# router.net
KiCad netlist of a schematic drawn in EAGLE
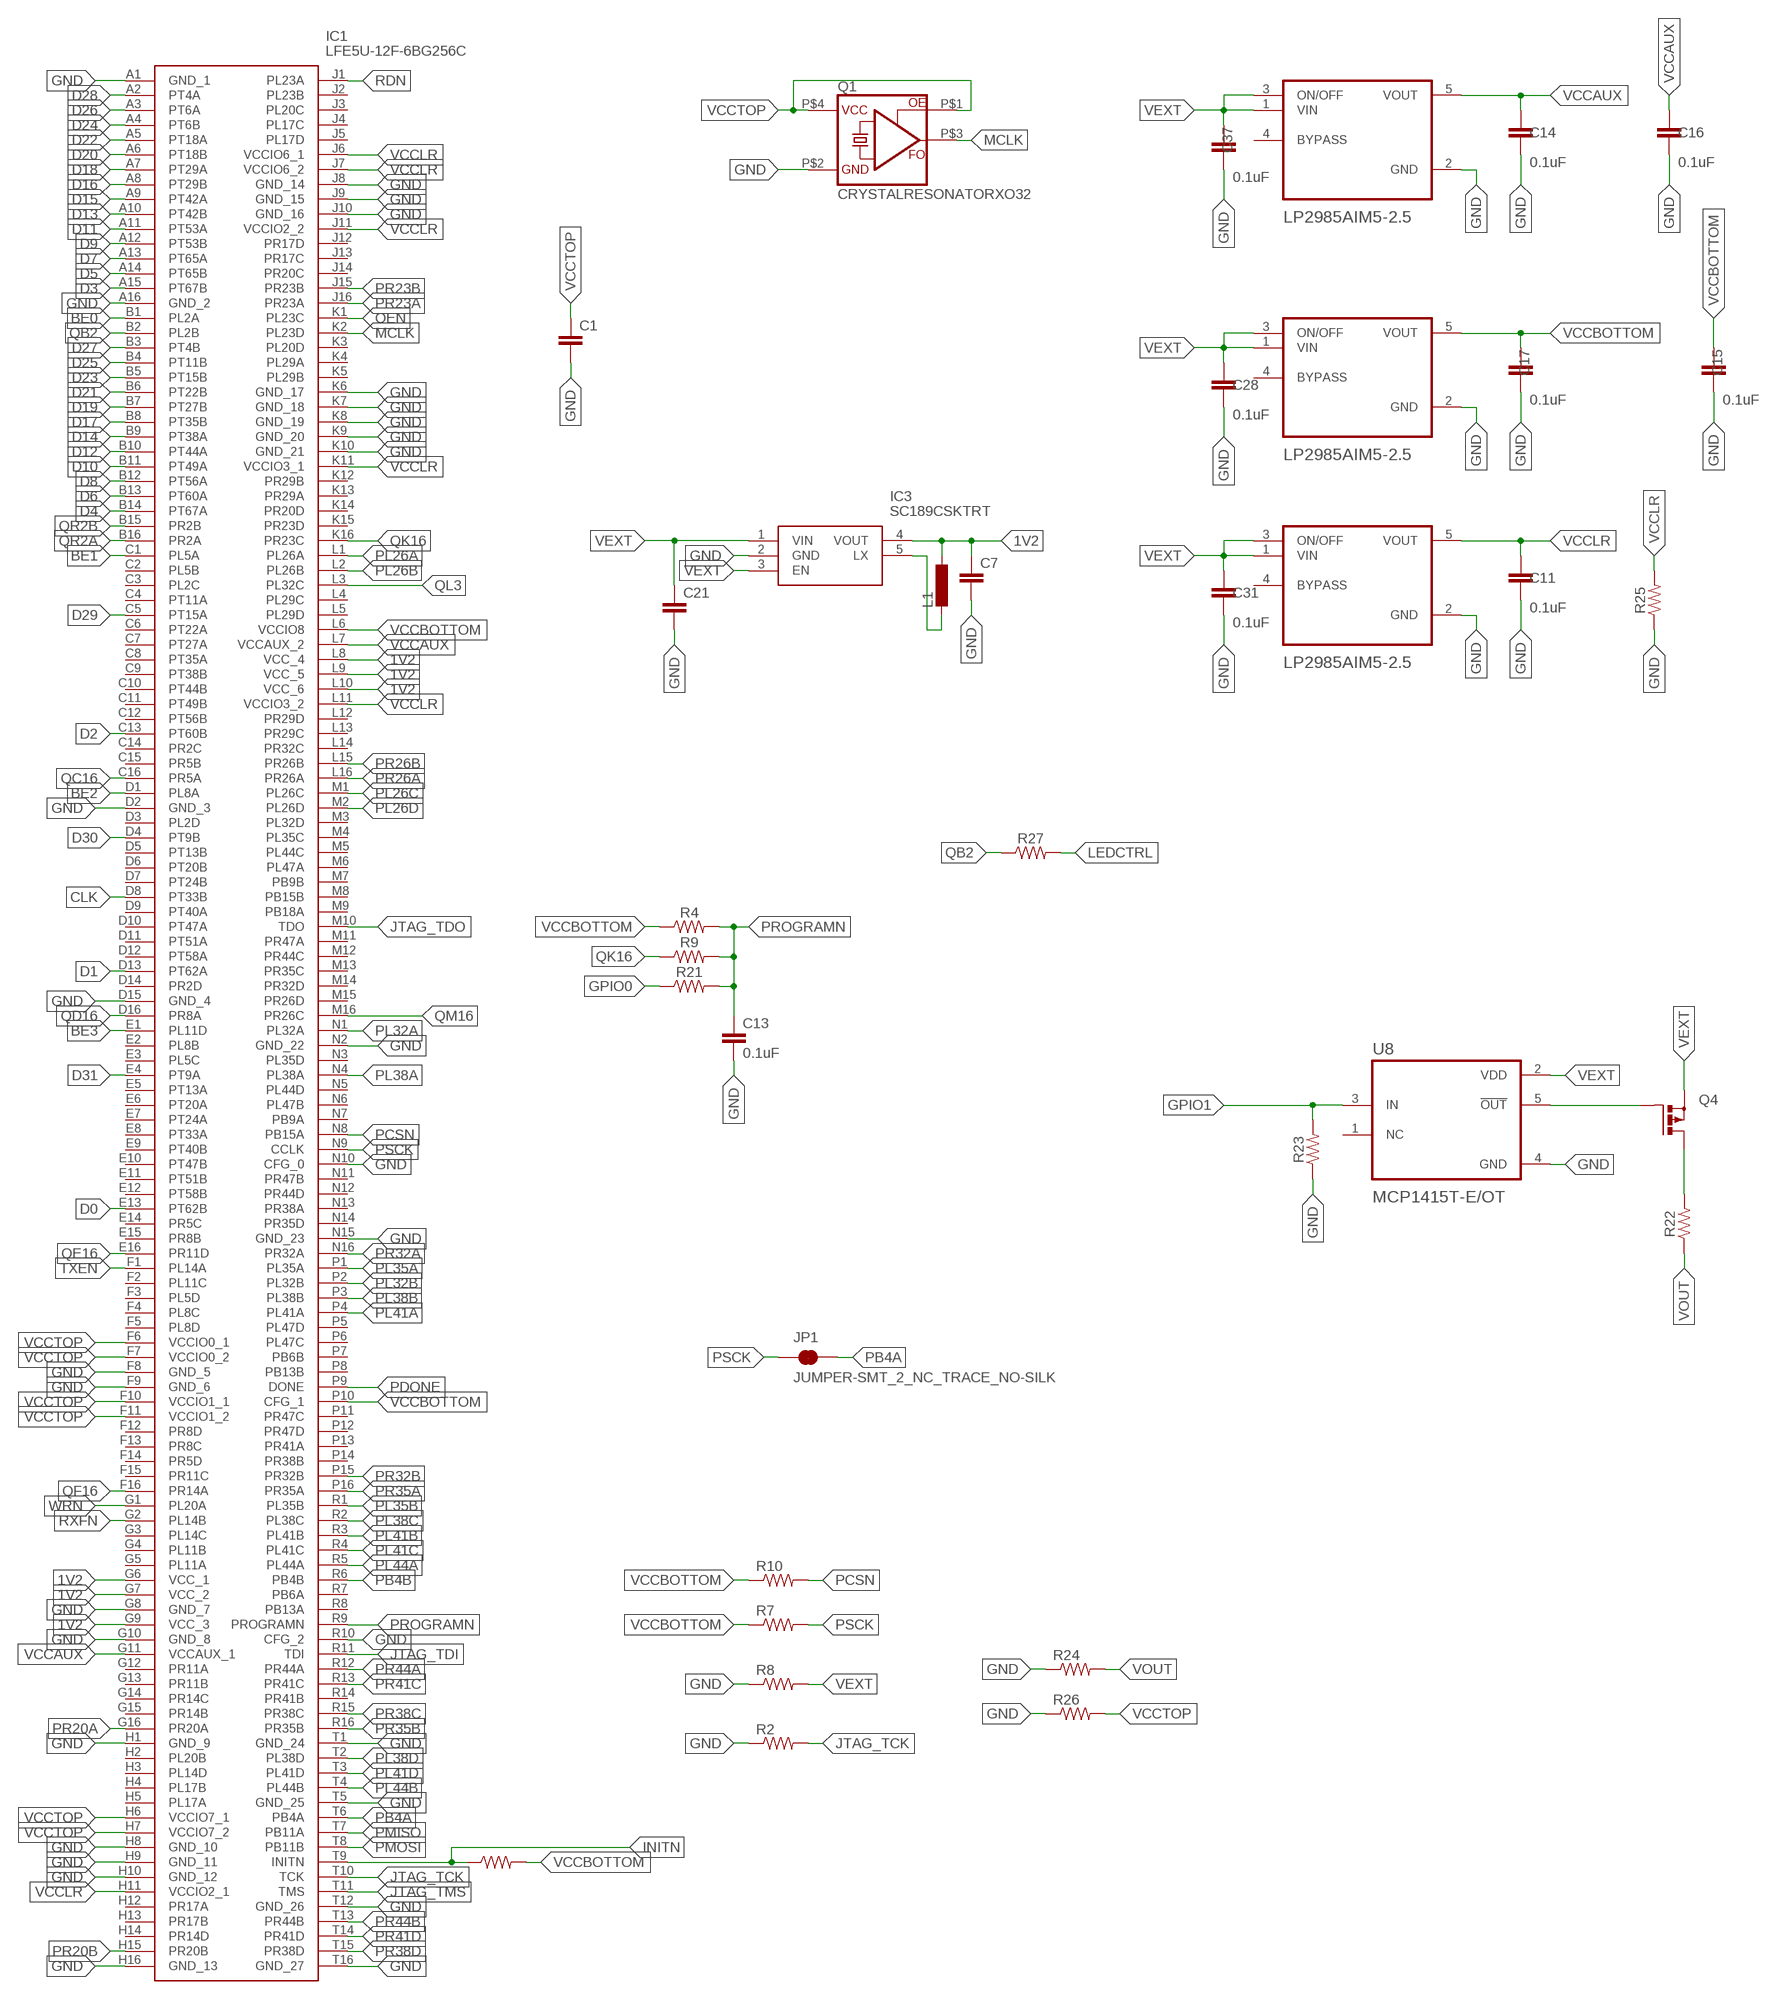
[diagram p0: schematic, sheet 1, part 1 of 3]
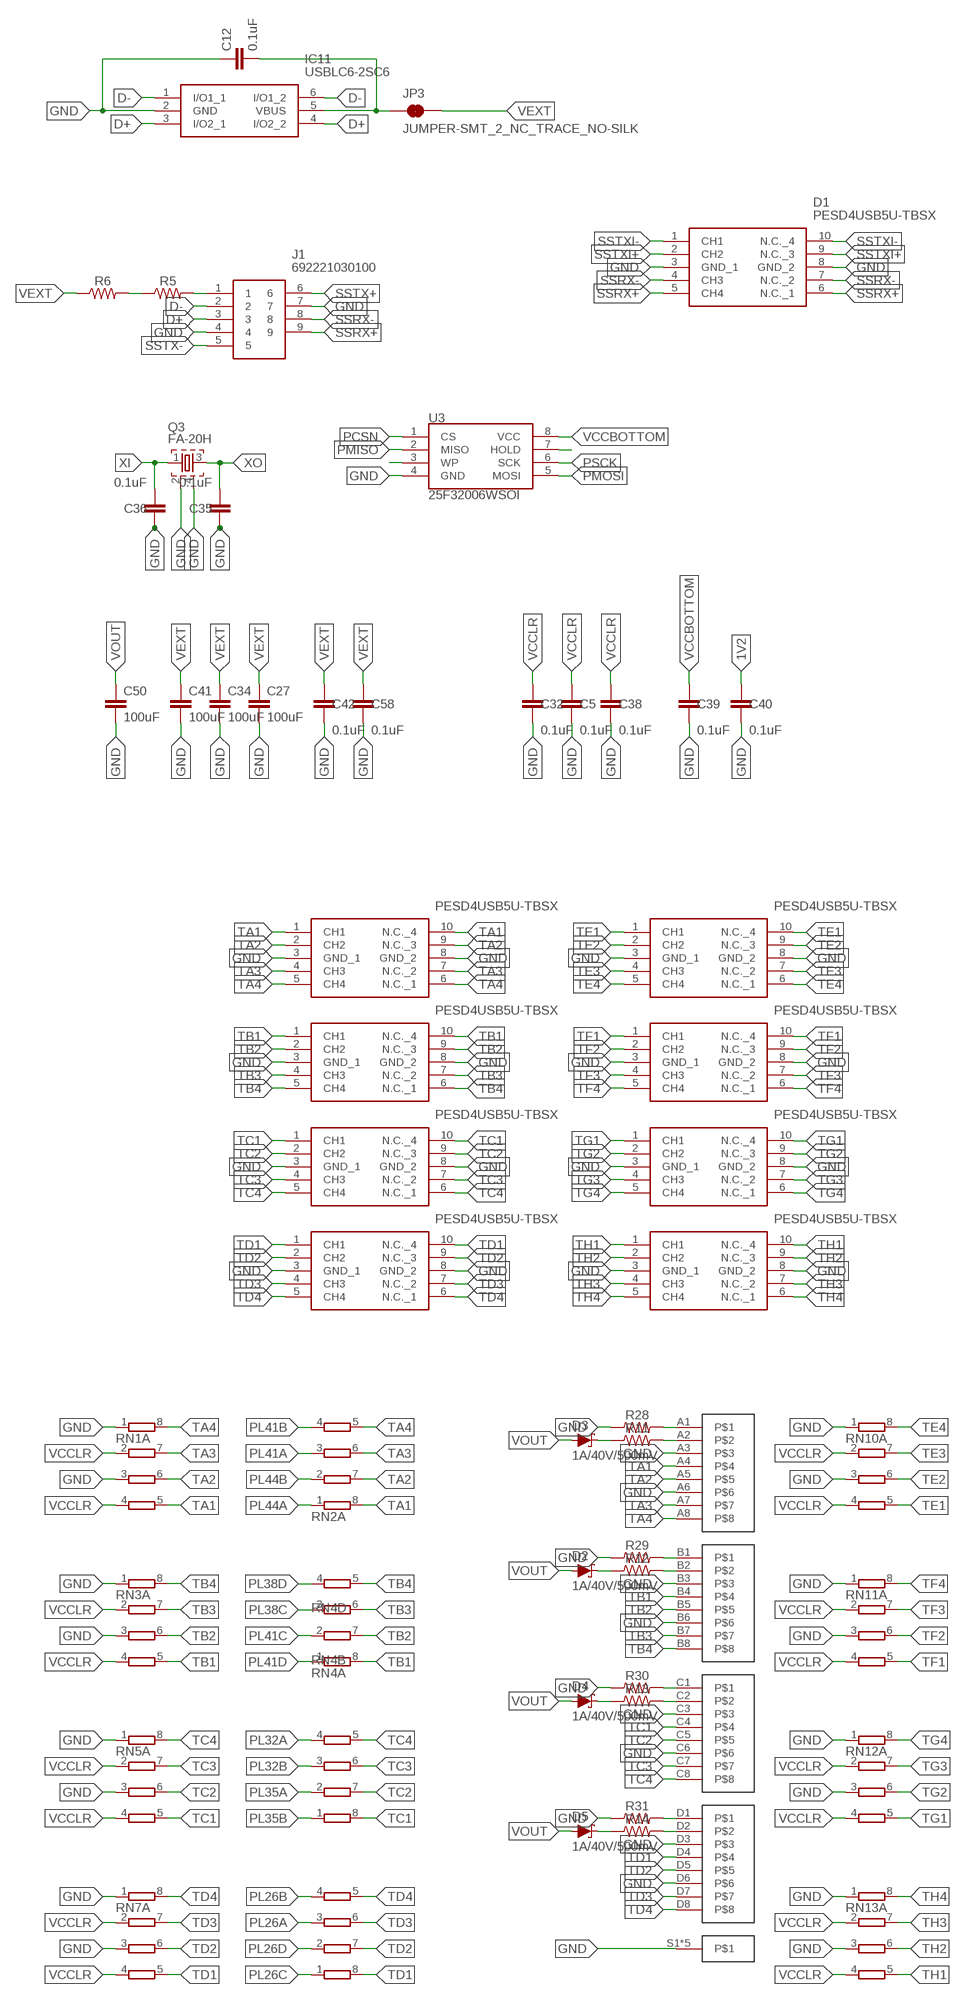
[diagram p1: schematic, sheet 1, part 2 of 3]
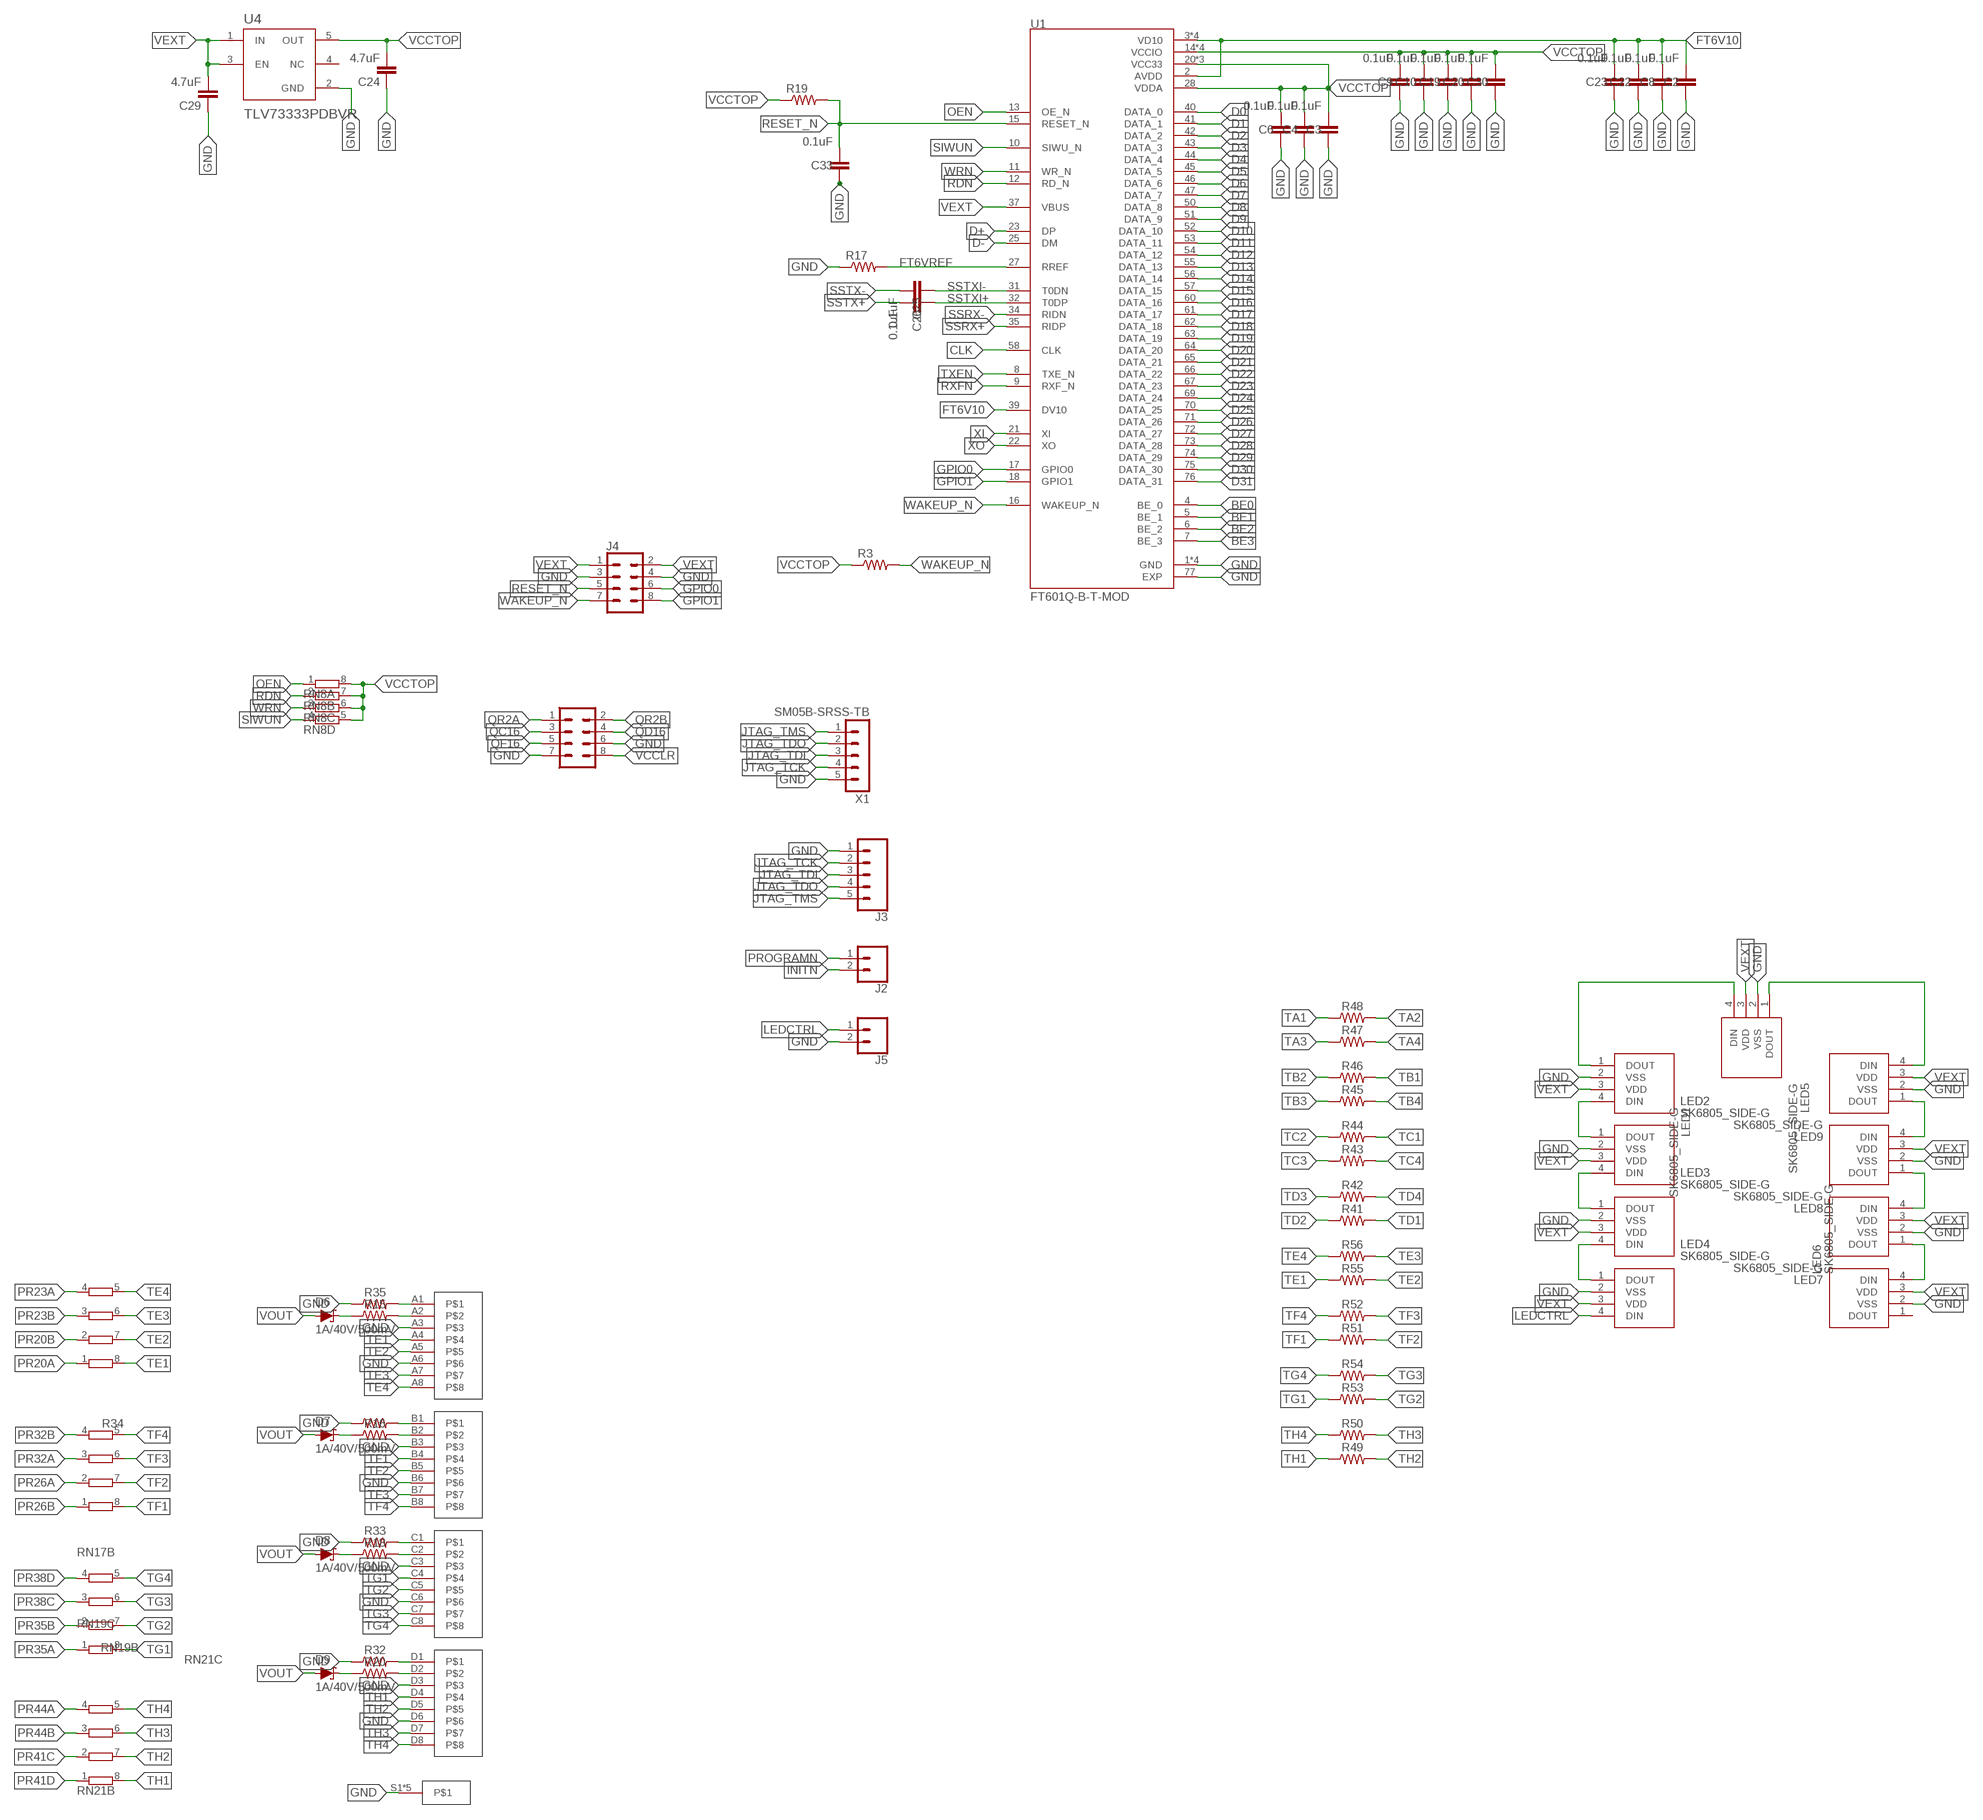
[diagram p2: schematic, sheet 1, part 3 of 3]

(export (version "E")
  (design (tool "Eeschema 10.0.6"))
  (components
    (comp (ref "C1")
      (value "C-EUC0603")
      (footprint "eagle-import:C0603")
      (libsource (lib "eagle-import") (part "resistor_348_C-EUC0603"))
    )
    (comp (ref "C2")
      (value "0.1uF")
      (footprint "eagle-import:0603")
      (libsource (lib "eagle-import") (part "0.1UF-0603-25V-5%"))
    )
    (comp (ref "C3")
      (value "0.1uF")
      (footprint "eagle-import:0603")
      (libsource (lib "eagle-import") (part "0.1UF-0603-25V-5%"))
    )
    (comp (ref "C4")
      (value "0.1uF")
      (footprint "eagle-import:0603")
      (libsource (lib "eagle-import") (part "0.1UF-0603-25V-5%"))
    )
    (comp (ref "C5")
      (value "0.1uF")
      (footprint "eagle-import:0603")
      (libsource (lib "eagle-import") (part "0.1UF-0603-25V-5%"))
    )
    (comp (ref "C6")
      (value "0.1uF")
      (footprint "eagle-import:0603")
      (libsource (lib "eagle-import") (part "0.1UF-0603-25V-5%"))
    )
    (comp (ref "C7")
      (value "C-EUC0805")
      (footprint "eagle-import:C0805")
      (libsource (lib "eagle-import") (part "resistor_348_C-EUC0805"))
    )
    (comp (ref "C8")
      (value "0.1uF")
      (footprint "eagle-import:0603")
      (libsource (lib "eagle-import") (part "0.1UF-0603-100V-10%"))
    )
    (comp (ref "C9")
      (value "0.1uF")
      (footprint "eagle-import:0603")
      (libsource (lib "eagle-import") (part "0.1UF-0603-100V-10%"))
    )
    (comp (ref "C10")
      (value "0.1uF")
      (footprint "eagle-import:0603")
      (libsource (lib "eagle-import") (part "0.1UF-0603-100V-10%"))
    )
    (comp (ref "C11")
      (value "0.1uF")
      (footprint "eagle-import:0603")
      (libsource (lib "eagle-import") (part "0.1UF-0603-25V-5%"))
    )
    (comp (ref "C12")
      (value "0.1uF")
      (footprint "eagle-import:0603")
      (libsource (lib "eagle-import") (part "0.1UF-0603-25V-(+80/-20%)"))
    )
    (comp (ref "C13")
      (value "0.1uF")
      (footprint "eagle-import:0603")
      (libsource (lib "eagle-import") (part "0.1UF-0603-25V-5%"))
    )
    (comp (ref "C14")
      (value "0.1uF")
      (footprint "eagle-import:0603")
      (libsource (lib "eagle-import") (part "0.1UF-0603-25V-5%"))
    )
    (comp (ref "C15")
      (value "0.1uF")
      (footprint "eagle-import:0603")
      (libsource (lib "eagle-import") (part "0.1UF-0603-25V-5%"))
    )
    (comp (ref "C16")
      (value "0.1uF")
      (footprint "eagle-import:0603")
      (libsource (lib "eagle-import") (part "0.1UF-0603-25V-5%"))
    )
    (comp (ref "C17")
      (value "0.1uF")
      (footprint "eagle-import:0603")
      (libsource (lib "eagle-import") (part "0.1UF-0603-25V-5%"))
    )
    (comp (ref "C19")
      (value "0.1uF")
      (footprint "eagle-import:0603")
      (libsource (lib "eagle-import") (part "0.1UF-0603-100V-10%"))
    )
    (comp (ref "C20")
      (value "0.1uF")
      (footprint "eagle-import:0603")
      (libsource (lib "eagle-import") (part "0.1UF-0603-100V-10%"))
    )
    (comp (ref "C21")
      (value "C-EUC0805")
      (footprint "eagle-import:C0805")
      (libsource (lib "eagle-import") (part "resistor_348_C-EUC0805"))
    )
    (comp (ref "C22")
      (value "0.1uF")
      (footprint "eagle-import:0603")
      (libsource (lib "eagle-import") (part "0.1UF-0603-25V-5%"))
    )
    (comp (ref "C23")
      (value "0.1uF")
      (footprint "eagle-import:0603")
      (libsource (lib "eagle-import") (part "0.1UF-0603-100V-10%"))
    )
    (comp (ref "C24")
      (value "4.7uF")
      (footprint "eagle-import:C0603")
      (libsource (lib "eagle-import") (part "C-EUC0603"))
    )
    (comp (ref "C25")
      (value "0.1uF")
      (footprint "eagle-import:0603")
      (libsource (lib "eagle-import") (part "0.1UF-0603-25V-5%"))
    )
    (comp (ref "C26")
      (value "0.1uF")
      (footprint "eagle-import:0603")
      (libsource (lib "eagle-import") (part "0.1UF-0603-25V-5%"))
    )
    (comp (ref "C27")
      (value "100uF")
      (footprint "eagle-import:C1210")
      (libsource (lib "eagle-import") (part "C-EUC1210"))
    )
    (comp (ref "C28")
      (value "0.1uF")
      (footprint "eagle-import:0603")
      (libsource (lib "eagle-import") (part "0.1UF-0603-25V-5%"))
    )
    (comp (ref "C29")
      (value "4.7uF")
      (footprint "eagle-import:C0603")
      (libsource (lib "eagle-import") (part "C-EUC0603"))
    )
    (comp (ref "C30")
      (value "0.1uF")
      (footprint "eagle-import:0603")
      (libsource (lib "eagle-import") (part "0.1UF-0603-100V-10%"))
    )
    (comp (ref "C31")
      (value "0.1uF")
      (footprint "eagle-import:0603")
      (libsource (lib "eagle-import") (part "0.1UF-0603-25V-5%"))
    )
    (comp (ref "C32")
      (value "0.1uF")
      (footprint "eagle-import:0603")
      (libsource (lib "eagle-import") (part "0.1UF-0603-25V-5%"))
    )
    (comp (ref "C33")
      (value "0.1uF")
      (footprint "eagle-import:0603")
      (libsource (lib "eagle-import") (part "0.1UF-0603-25V-5%"))
    )
    (comp (ref "C34")
      (value "100uF")
      (footprint "eagle-import:C1210")
      (libsource (lib "eagle-import") (part "C-EUC1210"))
    )
    (comp (ref "C35")
      (value "0.1uF")
      (footprint "eagle-import:0603")
      (libsource (lib "eagle-import") (part "0.1UF-0603-25V-5%"))
    )
    (comp (ref "C36")
      (value "0.1uF")
      (footprint "eagle-import:0603")
      (libsource (lib "eagle-import") (part "0.1UF-0603-25V-5%"))
    )
    (comp (ref "C37")
      (value "0.1uF")
      (footprint "eagle-import:0603")
      (libsource (lib "eagle-import") (part "0.1UF-0603-25V-5%"))
    )
    (comp (ref "C38")
      (value "0.1uF")
      (footprint "eagle-import:0603")
      (libsource (lib "eagle-import") (part "0.1UF-0603-25V-5%"))
    )
    (comp (ref "C39")
      (value "0.1uF")
      (footprint "eagle-import:0603")
      (libsource (lib "eagle-import") (part "0.1UF-0603-25V-5%"))
    )
    (comp (ref "C40")
      (value "0.1uF")
      (footprint "eagle-import:0603")
      (libsource (lib "eagle-import") (part "0.1UF-0603-25V-5%"))
    )
    (comp (ref "C41")
      (value "100uF")
      (footprint "eagle-import:C1210")
      (libsource (lib "eagle-import") (part "C-EUC1210"))
    )
    (comp (ref "C42")
      (value "0.1uF")
      (footprint "eagle-import:0603")
      (libsource (lib "eagle-import") (part "0.1UF-0603-25V-5%"))
    )
    (comp (ref "C50")
      (value "100uF")
      (footprint "eagle-import:C1210")
      (libsource (lib "eagle-import") (part "C-EUC1210"))
    )
    (comp (ref "C58")
      (value "0.1uF")
      (footprint "eagle-import:0603")
      (libsource (lib "eagle-import") (part "0.1UF-0603-25V-5%"))
    )
    (comp (ref "D1")
      (value "PESD4USB5U-TBSX")
      (footprint "eagle-import:SON50P100X250X80-10N")
      (fields (field (name "MOUSER_PART_NUMBER") "771-PESD4USB5U-TBSX"))
      (libsource (lib "eagle-import") (part "PESD4USB5U-TBSX"))
    )
    (comp (ref "D2")
      (value "1A/40V/500mV")
      (footprint "eagle-import:SMA-DIODE")
      (libsource (lib "eagle-import") (part "DIODE-SCHOTTKY-SS14"))
    )
    (comp (ref "D3")
      (value "1A/40V/500mV")
      (footprint "eagle-import:SMA-DIODE")
      (libsource (lib "eagle-import") (part "DIODE-SCHOTTKY-SS14"))
    )
    (comp (ref "D4")
      (value "1A/40V/500mV")
      (footprint "eagle-import:SMA-DIODE")
      (libsource (lib "eagle-import") (part "DIODE-SCHOTTKY-SS14"))
    )
    (comp (ref "D5")
      (value "1A/40V/500mV")
      (footprint "eagle-import:SMA-DIODE")
      (libsource (lib "eagle-import") (part "DIODE-SCHOTTKY-SS14"))
    )
    (comp (ref "D6")
      (value "1A/40V/500mV")
      (footprint "eagle-import:SMA-DIODE")
      (libsource (lib "eagle-import") (part "DIODE-SCHOTTKY-SS14"))
    )
    (comp (ref "D7")
      (value "1A/40V/500mV")
      (footprint "eagle-import:SMA-DIODE")
      (libsource (lib "eagle-import") (part "DIODE-SCHOTTKY-SS14"))
    )
    (comp (ref "D8")
      (value "1A/40V/500mV")
      (footprint "eagle-import:SMA-DIODE")
      (libsource (lib "eagle-import") (part "DIODE-SCHOTTKY-SS14"))
    )
    (comp (ref "D9")
      (value "1A/40V/500mV")
      (footprint "eagle-import:SMA-DIODE")
      (libsource (lib "eagle-import") (part "DIODE-SCHOTTKY-SS14"))
    )
    (comp (ref "D10")
      (value "PESD4USB5U-TBSX")
      (footprint "eagle-import:SON50P100X250X80-10N")
      (fields (field (name "MOUSER_PART_NUMBER") "771-PESD4USB5U-TBSX"))
      (libsource (lib "eagle-import") (part "PESD4USB5U-TBSX"))
    )
    (comp (ref "D11")
      (value "PESD4USB5U-TBSX")
      (footprint "eagle-import:SON50P100X250X80-10N")
      (fields (field (name "MOUSER_PART_NUMBER") "771-PESD4USB5U-TBSX"))
      (libsource (lib "eagle-import") (part "PESD4USB5U-TBSX"))
    )
    (comp (ref "D12")
      (value "PESD4USB5U-TBSX")
      (footprint "eagle-import:SON50P100X250X80-10N")
      (fields (field (name "MOUSER_PART_NUMBER") "771-PESD4USB5U-TBSX"))
      (libsource (lib "eagle-import") (part "PESD4USB5U-TBSX"))
    )
    (comp (ref "D13")
      (value "PESD4USB5U-TBSX")
      (footprint "eagle-import:SON50P100X250X80-10N")
      (fields (field (name "MOUSER_PART_NUMBER") "771-PESD4USB5U-TBSX"))
      (libsource (lib "eagle-import") (part "PESD4USB5U-TBSX"))
    )
    (comp (ref "D14")
      (value "PESD4USB5U-TBSX")
      (footprint "eagle-import:SON50P100X250X80-10N")
      (fields (field (name "MOUSER_PART_NUMBER") "771-PESD4USB5U-TBSX"))
      (libsource (lib "eagle-import") (part "PESD4USB5U-TBSX"))
    )
    (comp (ref "D15")
      (value "PESD4USB5U-TBSX")
      (footprint "eagle-import:SON50P100X250X80-10N")
      (fields (field (name "MOUSER_PART_NUMBER") "771-PESD4USB5U-TBSX"))
      (libsource (lib "eagle-import") (part "PESD4USB5U-TBSX"))
    )
    (comp (ref "D16")
      (value "PESD4USB5U-TBSX")
      (footprint "eagle-import:SON50P100X250X80-10N")
      (fields (field (name "MOUSER_PART_NUMBER") "771-PESD4USB5U-TBSX"))
      (libsource (lib "eagle-import") (part "PESD4USB5U-TBSX"))
    )
    (comp (ref "D17")
      (value "PESD4USB5U-TBSX")
      (footprint "eagle-import:SON50P100X250X80-10N")
      (fields (field (name "MOUSER_PART_NUMBER") "771-PESD4USB5U-TBSX"))
      (libsource (lib "eagle-import") (part "PESD4USB5U-TBSX"))
    )
    (comp (ref "IC1")
      (value "LFE5U-12F-6BG256C")
      (footprint "eagle-import:BGA256C80P16X16_1400X1400X170")
      (fields (field (name "MF") "Lattice Semiconductor"))
      (libsource (lib "eagle-import") (part "LFE5U-12F-6BG256C"))
    )
    (comp (ref "IC3")
      (value "SC189CSKTRT")
      (footprint "eagle-import:SOT95P280X145-5N")
      (fields (field (name "MOUSER_PART_NUMBER") "947-SC189CSKTRT"))
      (libsource (lib "eagle-import") (part "SC189CSKTRT"))
    )
    (comp (ref "IC11")
      (value "USBLC6-2SC6")
      (footprint "eagle-import:SOT95P280X145-6N")
      (fields (field (name "MOUSER_PART_NUMBER") "511-USBLC6-2SC6"))
      (libsource (lib "eagle-import") (part "USBLC6-2SC6"))
    )
    (comp (ref "J1")
      (value "692221030100")
      (footprint "eagle-import:WR-COM_USB_TYPE_B")
      (fields (field (name "MOUSER_PART_NUMBER") "710-692221030100"))
      (libsource (lib "eagle-import") (part "692221030100"))
    )
    (comp (ref "J2")
      (value "CONN_02")
      (footprint "eagle-import:1X02")
      (libsource (lib "eagle-import") (part "CONN_02"))
    )
    (comp (ref "J3")
      (value "CONN_05")
      (footprint "eagle-import:1X05")
      (libsource (lib "eagle-import") (part "CONN_05"))
    )
    (comp (ref "J4")
      (value "CONN_04X2")
      (footprint "eagle-import:2X4")
      (libsource (lib "eagle-import") (part "CONN_04X2"))
    )
    (comp (ref "J5")
      (value "CONN_02")
      (footprint "eagle-import:1X02")
      (libsource (lib "eagle-import") (part "CONN_02"))
    )
    (comp (ref "J8")
      (value "CONN_04X2")
      (footprint "eagle-import:2X4")
      (libsource (lib "eagle-import") (part "CONN_04X2"))
    )
    (comp (ref "JP1")
      (value "JUMPER-SMT_2_NC_TRACE_NO-SILK")
      (footprint "eagle-import:SMT-JUMPER_2_NC_TRACE_NO-SILK")
      (libsource (lib "eagle-import") (part "JUMPER-SMT_2_NC_TRACE_NO-SILK"))
    )
    (comp (ref "JP3")
      (value "JUMPER-SMT_2_NC_TRACE_NO-SILK")
      (footprint "eagle-import:SMT-JUMPER_2_NC_TRACE_NO-SILK")
      (libsource (lib "eagle-import") (part "JUMPER-SMT_2_NC_TRACE_NO-SILK"))
    )
    (comp (ref "L1")
      (value "L-EUL3230M")
      (footprint "eagle-import:L3230M")
      (libsource (lib "eagle-import") (part "L-EUL3230M"))
    )
    (comp (ref "LED1")
      (value "SK6805_SIDE-G")
      (footprint "eagle-import:SK6805SIDEG")
      (fields (field (name "MANUFACTURER_PART_NUMBER") "SK6805 SIDE-G"))
      (libsource (lib "eagle-import") (part "SK6805_SIDE-G"))
    )
    (comp (ref "LED2")
      (value "SK6805_SIDE-G")
      (footprint "eagle-import:SK6805SIDEG")
      (fields (field (name "MANUFACTURER_PART_NUMBER") "SK6805 SIDE-G"))
      (libsource (lib "eagle-import") (part "SK6805_SIDE-G"))
    )
    (comp (ref "LED3")
      (value "SK6805_SIDE-G")
      (footprint "eagle-import:SK6805SIDEG")
      (fields (field (name "MANUFACTURER_PART_NUMBER") "SK6805 SIDE-G"))
      (libsource (lib "eagle-import") (part "SK6805_SIDE-G"))
    )
    (comp (ref "LED4")
      (value "SK6805_SIDE-G")
      (footprint "eagle-import:SK6805SIDEG")
      (fields (field (name "MANUFACTURER_PART_NUMBER") "SK6805 SIDE-G"))
      (libsource (lib "eagle-import") (part "SK6805_SIDE-G"))
    )
    (comp (ref "LED5")
      (value "SK6805_SIDE-G")
      (footprint "eagle-import:SK6805SIDEG")
      (fields (field (name "MANUFACTURER_PART_NUMBER") "SK6805 SIDE-G"))
      (libsource (lib "eagle-import") (part "SK6805_SIDE-G"))
    )
    (comp (ref "LED6")
      (value "SK6805_SIDE-G")
      (footprint "eagle-import:SK6805SIDEG")
      (fields (field (name "MANUFACTURER_PART_NUMBER") "SK6805 SIDE-G"))
      (libsource (lib "eagle-import") (part "SK6805_SIDE-G"))
    )
    (comp (ref "LED7")
      (value "SK6805_SIDE-G")
      (footprint "eagle-import:SK6805SIDEG")
      (fields (field (name "MANUFACTURER_PART_NUMBER") "SK6805 SIDE-G"))
      (libsource (lib "eagle-import") (part "SK6805_SIDE-G"))
    )
    (comp (ref "LED8")
      (value "SK6805_SIDE-G")
      (footprint "eagle-import:SK6805SIDEG")
      (fields (field (name "MANUFACTURER_PART_NUMBER") "SK6805 SIDE-G"))
      (libsource (lib "eagle-import") (part "SK6805_SIDE-G"))
    )
    (comp (ref "LED9")
      (value "SK6805_SIDE-G")
      (footprint "eagle-import:SK6805SIDEG")
      (fields (field (name "MANUFACTURER_PART_NUMBER") "SK6805 SIDE-G"))
      (libsource (lib "eagle-import") (part "SK6805_SIDE-G"))
    )
    (comp (ref "Q1")
      (value "CRYSTALRESONATORXO32")
      (footprint "eagle-import:XO32")
      (libsource (lib "eagle-import") (part "CRYSTALRESONATORXO32"))
    )
    (comp (ref "Q3")
      (value "FA-20H")
      (footprint "eagle-import:FA-20H")
      (libsource (lib "eagle-import") (part "FA-20H"))
    )
    (comp (ref "Q4")
      (value "P-MOSFET-SO8")
      (footprint "eagle-import:SO-08")
      (libsource (lib "eagle-import") (part "P-MOSFET-SO8"))
    )
    (comp (ref "R1")
      (value "RESISTOR0603")
      (footprint "eagle-import:0603")
      (libsource (lib "eagle-import") (part "RESISTOR0603"))
    )
    (comp (ref "R2")
      (value "RESISTOR0603")
      (footprint "eagle-import:0603")
      (libsource (lib "eagle-import") (part "RESISTOR0603"))
    )
    (comp (ref "R3")
      (value "RESISTOR0603")
      (footprint "eagle-import:0603")
      (libsource (lib "eagle-import") (part "RESISTOR0603"))
    )
    (comp (ref "R4")
      (value "RESISTOR0603")
      (footprint "eagle-import:0603")
      (libsource (lib "eagle-import") (part "RESISTOR0603"))
    )
    (comp (ref "R5")
      (value "RESISTOR0805")
      (footprint "eagle-import:0805")
      (libsource (lib "eagle-import") (part "RESISTOR0805"))
    )
    (comp (ref "R6")
      (value "RESISTOR0805")
      (footprint "eagle-import:0805")
      (libsource (lib "eagle-import") (part "RESISTOR0805"))
    )
    (comp (ref "R7")
      (value "RESISTOR0603")
      (footprint "eagle-import:0603")
      (libsource (lib "eagle-import") (part "RESISTOR0603"))
    )
    (comp (ref "R8")
      (value "RESISTOR0603")
      (footprint "eagle-import:0603")
      (libsource (lib "eagle-import") (part "RESISTOR0603"))
    )
    (comp (ref "R9")
      (value "RESISTOR0603")
      (footprint "eagle-import:0603")
      (libsource (lib "eagle-import") (part "RESISTOR0603"))
    )
    (comp (ref "R10")
      (value "RESISTOR0603")
      (footprint "eagle-import:0603")
      (libsource (lib "eagle-import") (part "RESISTOR0603"))
    )
    (comp (ref "R11")
      (value "RESISTOR0805")
      (footprint "eagle-import:0805")
      (libsource (lib "eagle-import") (part "RESISTOR0805"))
    )
    (comp (ref "R12")
      (value "RESISTOR0805")
      (footprint "eagle-import:0805")
      (libsource (lib "eagle-import") (part "RESISTOR0805"))
    )
    (comp (ref "R13")
      (value "RESISTOR0805")
      (footprint "eagle-import:0805")
      (libsource (lib "eagle-import") (part "RESISTOR0805"))
    )
    (comp (ref "R14")
      (value "RESISTOR0805")
      (footprint "eagle-import:0805")
      (libsource (lib "eagle-import") (part "RESISTOR0805"))
    )
    (comp (ref "R15")
      (value "RESISTOR0805")
      (footprint "eagle-import:0805")
      (libsource (lib "eagle-import") (part "RESISTOR0805"))
    )
    (comp (ref "R16")
      (value "RESISTOR0805")
      (footprint "eagle-import:0805")
      (libsource (lib "eagle-import") (part "RESISTOR0805"))
    )
    (comp (ref "R17")
      (value "RESISTOR0603")
      (footprint "eagle-import:0603")
      (libsource (lib "eagle-import") (part "RESISTOR0603"))
    )
    (comp (ref "R18")
      (value "RESISTOR0805")
      (footprint "eagle-import:0805")
      (libsource (lib "eagle-import") (part "RESISTOR0805"))
    )
    (comp (ref "R19")
      (value "RESISTOR0603")
      (footprint "eagle-import:0603")
      (libsource (lib "eagle-import") (part "RESISTOR0603"))
    )
    (comp (ref "R20")
      (value "RESISTOR0805")
      (footprint "eagle-import:0805")
      (libsource (lib "eagle-import") (part "RESISTOR0805"))
    )
    (comp (ref "R21")
      (value "RESISTOR0603")
      (footprint "eagle-import:0603")
      (libsource (lib "eagle-import") (part "RESISTOR0603"))
    )
    (comp (ref "R22")
      (value "RESISTOR1206")
      (footprint "eagle-import:1206")
      (libsource (lib "eagle-import") (part "RESISTOR1206"))
    )
    (comp (ref "R23")
      (value "RESISTOR0603")
      (footprint "eagle-import:0603")
      (libsource (lib "eagle-import") (part "RESISTOR0603"))
    )
    (comp (ref "R24")
      (value "RESISTOR0603")
      (footprint "eagle-import:0603")
      (libsource (lib "eagle-import") (part "RESISTOR0603"))
    )
    (comp (ref "R25")
      (value "RESISTOR0603")
      (footprint "eagle-import:0603")
      (libsource (lib "eagle-import") (part "RESISTOR0603"))
    )
    (comp (ref "R26")
      (value "RESISTOR0603")
      (footprint "eagle-import:0603")
      (libsource (lib "eagle-import") (part "RESISTOR0603"))
    )
    (comp (ref "R27")
      (value "RESISTOR0603")
      (footprint "eagle-import:0603")
      (libsource (lib "eagle-import") (part "RESISTOR0603"))
    )
    (comp (ref "R28")
      (value "RESISTOR0603")
      (footprint "eagle-import:0603")
      (libsource (lib "eagle-import") (part "RESISTOR0603"))
    )
    (comp (ref "R29")
      (value "RESISTOR0603")
      (footprint "eagle-import:0603")
      (libsource (lib "eagle-import") (part "RESISTOR0603"))
    )
    (comp (ref "R30")
      (value "RESISTOR0603")
      (footprint "eagle-import:0603")
      (libsource (lib "eagle-import") (part "RESISTOR0603"))
    )
    (comp (ref "R31")
      (value "RESISTOR0603")
      (footprint "eagle-import:0603")
      (libsource (lib "eagle-import") (part "RESISTOR0603"))
    )
    (comp (ref "R32")
      (value "RESISTOR0603")
      (footprint "eagle-import:0603")
      (libsource (lib "eagle-import") (part "RESISTOR0603"))
    )
    (comp (ref "R33")
      (value "RESISTOR0603")
      (footprint "eagle-import:0603")
      (libsource (lib "eagle-import") (part "RESISTOR0603"))
    )
    (comp (ref "R34")
      (value "RESISTOR0603")
      (footprint "eagle-import:0603")
      (libsource (lib "eagle-import") (part "RESISTOR0603"))
    )
    (comp (ref "R35")
      (value "RESISTOR0603")
      (footprint "eagle-import:0603")
      (libsource (lib "eagle-import") (part "RESISTOR0603"))
    )
    (comp (ref "R41")
      (value "RESISTOR0402")
      (footprint "eagle-import:0402")
      (libsource (lib "eagle-import") (part "RESISTOR0402"))
    )
    (comp (ref "R42")
      (value "RESISTOR0402")
      (footprint "eagle-import:0402")
      (libsource (lib "eagle-import") (part "RESISTOR0402"))
    )
    (comp (ref "R43")
      (value "RESISTOR0402")
      (footprint "eagle-import:0402")
      (libsource (lib "eagle-import") (part "RESISTOR0402"))
    )
    (comp (ref "R44")
      (value "RESISTOR0402")
      (footprint "eagle-import:0402")
      (libsource (lib "eagle-import") (part "RESISTOR0402"))
    )
    (comp (ref "R45")
      (value "RESISTOR0402")
      (footprint "eagle-import:0402")
      (libsource (lib "eagle-import") (part "RESISTOR0402"))
    )
    (comp (ref "R46")
      (value "RESISTOR0402")
      (footprint "eagle-import:0402")
      (libsource (lib "eagle-import") (part "RESISTOR0402"))
    )
    (comp (ref "R47")
      (value "RESISTOR0402")
      (footprint "eagle-import:0402")
      (libsource (lib "eagle-import") (part "RESISTOR0402"))
    )
    (comp (ref "R48")
      (value "RESISTOR0402")
      (footprint "eagle-import:0402")
      (libsource (lib "eagle-import") (part "RESISTOR0402"))
    )
    (comp (ref "R49")
      (value "RESISTOR0402")
      (footprint "eagle-import:0402")
      (libsource (lib "eagle-import") (part "RESISTOR0402"))
    )
    (comp (ref "R50")
      (value "RESISTOR0402")
      (footprint "eagle-import:0402")
      (libsource (lib "eagle-import") (part "RESISTOR0402"))
    )
    (comp (ref "R51")
      (value "RESISTOR0402")
      (footprint "eagle-import:0402")
      (libsource (lib "eagle-import") (part "RESISTOR0402"))
    )
    (comp (ref "R52")
      (value "RESISTOR0402")
      (footprint "eagle-import:0402")
      (libsource (lib "eagle-import") (part "RESISTOR0402"))
    )
    (comp (ref "R53")
      (value "RESISTOR0402")
      (footprint "eagle-import:0402")
      (libsource (lib "eagle-import") (part "RESISTOR0402"))
    )
    (comp (ref "R54")
      (value "RESISTOR0402")
      (footprint "eagle-import:0402")
      (libsource (lib "eagle-import") (part "RESISTOR0402"))
    )
    (comp (ref "R55")
      (value "RESISTOR0402")
      (footprint "eagle-import:0402")
      (libsource (lib "eagle-import") (part "RESISTOR0402"))
    )
    (comp (ref "R56")
      (value "RESISTOR0402")
      (footprint "eagle-import:0402")
      (libsource (lib "eagle-import") (part "RESISTOR0402"))
    )
    (comp (ref "RN1")
      (value "4R-NEXBV8V")
      (footprint "eagle-import:EXBV8V")
      (libsource (lib "eagle-import") (part "4R-NEXBV8V"))
    )
    (comp (ref "RN2")
      (value "4R-NEXBV8V")
      (footprint "eagle-import:EXBV8V")
      (libsource (lib "eagle-import") (part "4R-NEXBV8V"))
    )
    (comp (ref "RN3")
      (value "4R-NEXBV8V")
      (footprint "eagle-import:EXBV8V")
      (libsource (lib "eagle-import") (part "4R-NEXBV8V"))
    )
    (comp (ref "RN4")
      (value "4R-NEXBV8V")
      (footprint "eagle-import:EXBV8V")
      (libsource (lib "eagle-import") (part "4R-NEXBV8V"))
    )
    (comp (ref "RN5")
      (value "4R-NEXBV8V")
      (footprint "eagle-import:EXBV8V")
      (libsource (lib "eagle-import") (part "4R-NEXBV8V"))
    )
    (comp (ref "RN6")
      (value "4R-NEXBV8V")
      (footprint "eagle-import:EXBV8V")
      (libsource (lib "eagle-import") (part "4R-NEXBV8V"))
    )
    (comp (ref "RN7")
      (value "4R-NEXBV8V")
      (footprint "eagle-import:EXBV8V")
      (libsource (lib "eagle-import") (part "4R-NEXBV8V"))
    )
    (comp (ref "RN8")
      (value "4R-NEXBV8V")
      (footprint "eagle-import:EXBV8V")
      (libsource (lib "eagle-import") (part "4R-NEXBV8V"))
    )
    (comp (ref "RN9")
      (value "4R-NEXBV8V")
      (footprint "eagle-import:EXBV8V")
      (libsource (lib "eagle-import") (part "4R-NEXBV8V"))
    )
    (comp (ref "RN10")
      (value "4R-NEXBV8V")
      (footprint "eagle-import:EXBV8V")
      (libsource (lib "eagle-import") (part "4R-NEXBV8V"))
    )
    (comp (ref "RN11")
      (value "4R-NEXBV8V")
      (footprint "eagle-import:EXBV8V")
      (libsource (lib "eagle-import") (part "4R-NEXBV8V"))
    )
    (comp (ref "RN12")
      (value "4R-NEXBV8V")
      (footprint "eagle-import:EXBV8V")
      (libsource (lib "eagle-import") (part "4R-NEXBV8V"))
    )
    (comp (ref "RN13")
      (value "4R-NEXBV8V")
      (footprint "eagle-import:EXBV8V")
      (libsource (lib "eagle-import") (part "4R-NEXBV8V"))
    )
    (comp (ref "RN15")
      (value "4R-NEXBV8V")
      (footprint "eagle-import:EXBV8V")
      (libsource (lib "eagle-import") (part "4R-NEXBV8V"))
    )
    (comp (ref "RN17")
      (value "4R-NEXBV8V")
      (footprint "eagle-import:EXBV8V")
      (libsource (lib "eagle-import") (part "4R-NEXBV8V"))
    )
    (comp (ref "RN19")
      (value "4R-NEXBV8V")
      (footprint "eagle-import:EXBV8V")
      (libsource (lib "eagle-import") (part "4R-NEXBV8V"))
    )
    (comp (ref "RN21")
      (value "4R-NEXBV8V")
      (footprint "eagle-import:EXBV8V")
      (libsource (lib "eagle-import") (part "4R-NEXBV8V"))
    )
    (comp (ref "U$49")
      (value "QUADRJ45")
      (footprint "eagle-import:ARJ14A-MESA-MU2_CONN_ARJ14A-MESA-MU2")
      (libsource (lib "eagle-import") (part "QUADRJ45"))
    )
    (comp (ref "U$50")
      (value "QUADRJ45")
      (footprint "eagle-import:ARJ14A-MESA-MU2_CONN_ARJ14A-MESA-MU2")
      (libsource (lib "eagle-import") (part "QUADRJ45"))
    )
    (comp (ref "U1")
      (value "FT601Q-B-T-MOD")
      (footprint "eagle-import:QFN40P900X900X100-77N-MOD")
      (fields (field (name "MF") "FTDI, Future") (field (name "MP") "FT601Q-B-T"))
      (libsource (lib "eagle-import") (part "FT601Q-B-T-MOD"))
    )
    (comp (ref "U3")
      (value "25F32006WSOI")
      (footprint "eagle-import:SO08-EIAJ")
      (libsource (lib "eagle-import") (part "SPI_FLASH-X25XXSMD1"))
    )
    (comp (ref "U4")
      (value "TLV73333PDBVR")
      (footprint "eagle-import:SOT95P280X145-5N")
      (fields (field (name "MF") "Texas Instruments"))
      (libsource (lib "eagle-import") (part "TLV73333PDBVR"))
    )
    (comp (ref "U5")
      (value "LP2985AIM5-2.5")
      (footprint "eagle-import:SOT95P280X145-5N")
      (fields (field (name "MF") "Texas Instruments") (field (name "MP") "LP2985AIM5-2.5/NOPB"))
      (libsource (lib "eagle-import") (part "LP2985AIM5-2.5"))
    )
    (comp (ref "U6")
      (value "LP2985AIM5-2.5")
      (footprint "eagle-import:SOT95P280X145-5N")
      (fields (field (name "MF") "Texas Instruments") (field (name "MP") "LP2985AIM5-2.5/NOPB"))
      (libsource (lib "eagle-import") (part "LP2985AIM5-2.5"))
    )
    (comp (ref "U7")
      (value "LP2985AIM5-2.5")
      (footprint "eagle-import:SOT95P280X145-5N")
      (fields (field (name "MF") "Texas Instruments") (field (name "MP") "LP2985AIM5-2.5/NOPB"))
      (libsource (lib "eagle-import") (part "LP2985AIM5-2.5"))
    )
    (comp (ref "U8")
      (value "MCP1415T-E/OT")
      (footprint "eagle-import:SOT95P270X145-5N")
      (fields (field (name "MF") "Microchip"))
      (libsource (lib "eagle-import") (part "MCP1415T-E/OT"))
    )
    (comp (ref "X1")
      (value "SM05B-SRSS-TB")
      (footprint "eagle-import:SM05B-SRSS-TB")
      (libsource (lib "eagle-import") (part "SM05B-SRSS-TB"))
    )
  )
  (nets
    (net (code "1") (name "/FT6VREF") (class "Default")
      (node (ref "R17") (pin "2") (pinfunction "2_2") (pintype "passive"))
      (node (ref "U1") (pin "27") (pinfunction "RREF_27") (pintype "input"))
    )
    (net (code "2") (name "1V2") (class "Default")
      (node (ref "C40") (pin "1") (pinfunction "1_1") (pintype "passive"))
      (node (ref "C7") (pin "1") (pinfunction "1_1") (pintype "passive"))
      (node (ref "IC1") (pin "G6") (pinfunction "VCC_1_G6") (pintype "bidirectional"))
      (node (ref "IC1") (pin "G7") (pinfunction "VCC_2_G7") (pintype "bidirectional"))
      (node (ref "IC1") (pin "G9") (pinfunction "VCC_3_G9") (pintype "bidirectional"))
      (node (ref "IC1") (pin "L10") (pinfunction "VCC_6_L10") (pintype "bidirectional"))
      (node (ref "IC1") (pin "L8") (pinfunction "VCC_4_L8") (pintype "bidirectional"))
      (node (ref "IC1") (pin "L9") (pinfunction "VCC_5_L9") (pintype "bidirectional"))
      (node (ref "IC3") (pin "4") (pinfunction "VOUT_4") (pintype "bidirectional"))
      (node (ref "L1") (pin "1") (pinfunction "1_1") (pintype "passive"))
    )
    (net (code "3") (name "BE0") (class "Default")
      (node (ref "IC1") (pin "B1") (pinfunction "PL2A_B1") (pintype "bidirectional"))
      (node (ref "U1") (pin "4") (pinfunction "BE_0_4") (pintype "bidirectional"))
    )
    (net (code "4") (name "BE1") (class "Default")
      (node (ref "IC1") (pin "C1") (pinfunction "PL5A_C1") (pintype "bidirectional"))
      (node (ref "U1") (pin "5") (pinfunction "BE_1_5") (pintype "bidirectional"))
    )
    (net (code "5") (name "BE2") (class "Default")
      (node (ref "IC1") (pin "D1") (pinfunction "PL8A_D1") (pintype "bidirectional"))
      (node (ref "U1") (pin "6") (pinfunction "BE_2_6") (pintype "bidirectional"))
    )
    (net (code "6") (name "BE3") (class "Default")
      (node (ref "IC1") (pin "E1") (pinfunction "PL11D_E1") (pintype "bidirectional"))
      (node (ref "U1") (pin "7") (pinfunction "BE_3_7") (pintype "bidirectional"))
    )
    (net (code "7") (name "CLK") (class "Default")
      (node (ref "IC1") (pin "D8") (pinfunction "PT33B_D8") (pintype "bidirectional"))
      (node (ref "U1") (pin "58") (pinfunction "CLK_58") (pintype "output"))
    )
    (net (code "8") (name "D+") (class "Default")
      (node (ref "IC11") (pin "3") (pinfunction "I/O2_1_3") (pintype "bidirectional"))
      (node (ref "IC11") (pin "4") (pinfunction "I/O2_2_4") (pintype "bidirectional"))
      (node (ref "J1") (pin "3") (pinfunction "3_3") (pintype "bidirectional"))
      (node (ref "U1") (pin "23") (pinfunction "DP_23") (pintype "bidirectional"))
    )
    (net (code "9") (name "D-") (class "Default")
      (node (ref "IC11") (pin "1") (pinfunction "I/O1_1_1") (pintype "bidirectional"))
      (node (ref "IC11") (pin "6") (pinfunction "I/O1_2_6") (pintype "bidirectional"))
      (node (ref "J1") (pin "2") (pinfunction "2_2") (pintype "bidirectional"))
      (node (ref "U1") (pin "25") (pinfunction "DM_25") (pintype "bidirectional"))
    )
    (net (code "10") (name "D0") (class "Default")
      (node (ref "IC1") (pin "E13") (pinfunction "PT62B_E13") (pintype "bidirectional"))
      (node (ref "U1") (pin "40") (pinfunction "DATA_0_40") (pintype "bidirectional"))
    )
    (net (code "11") (name "D1") (class "Default")
      (node (ref "IC1") (pin "D13") (pinfunction "PT62A_D13") (pintype "bidirectional"))
      (node (ref "U1") (pin "41") (pinfunction "DATA_1_41") (pintype "bidirectional"))
    )
    (net (code "12") (name "D2") (class "Default")
      (node (ref "IC1") (pin "C13") (pinfunction "PT60B_C13") (pintype "bidirectional"))
      (node (ref "U1") (pin "42") (pinfunction "DATA_2_42") (pintype "bidirectional"))
    )
    (net (code "13") (name "D3") (class "Default")
      (node (ref "IC1") (pin "A15") (pinfunction "PT67B_A15") (pintype "bidirectional"))
      (node (ref "U1") (pin "43") (pinfunction "DATA_3_43") (pintype "bidirectional"))
    )
    (net (code "14") (name "D4") (class "Default")
      (node (ref "IC1") (pin "B14") (pinfunction "PT67A_B14") (pintype "bidirectional"))
      (node (ref "U1") (pin "44") (pinfunction "DATA_4_44") (pintype "bidirectional"))
    )
    (net (code "15") (name "D5") (class "Default")
      (node (ref "IC1") (pin "A14") (pinfunction "PT65B_A14") (pintype "bidirectional"))
      (node (ref "U1") (pin "45") (pinfunction "DATA_5_45") (pintype "bidirectional"))
    )
    (net (code "16") (name "D6") (class "Default")
      (node (ref "IC1") (pin "B13") (pinfunction "PT60A_B13") (pintype "bidirectional"))
      (node (ref "U1") (pin "46") (pinfunction "DATA_6_46") (pintype "bidirectional"))
    )
    (net (code "17") (name "D7") (class "Default")
      (node (ref "IC1") (pin "A13") (pinfunction "PT65A_A13") (pintype "bidirectional"))
      (node (ref "U1") (pin "47") (pinfunction "DATA_7_47") (pintype "bidirectional"))
    )
    (net (code "18") (name "D8") (class "Default")
      (node (ref "IC1") (pin "B12") (pinfunction "PT56A_B12") (pintype "bidirectional"))
      (node (ref "U1") (pin "50") (pinfunction "DATA_8_50") (pintype "bidirectional"))
    )
    (net (code "19") (name "D9") (class "Default")
      (node (ref "IC1") (pin "A12") (pinfunction "PT53B_A12") (pintype "bidirectional"))
      (node (ref "U1") (pin "51") (pinfunction "DATA_9_51") (pintype "bidirectional"))
    )
    (net (code "20") (name "D10") (class "Default")
      (node (ref "IC1") (pin "B11") (pinfunction "PT49A_B11") (pintype "bidirectional"))
      (node (ref "U1") (pin "52") (pinfunction "DATA_10_52") (pintype "bidirectional"))
    )
    (net (code "21") (name "D11") (class "Default")
      (node (ref "IC1") (pin "A11") (pinfunction "PT53A_A11") (pintype "bidirectional"))
      (node (ref "U1") (pin "53") (pinfunction "DATA_11_53") (pintype "bidirectional"))
    )
    (net (code "22") (name "D12") (class "Default")
      (node (ref "IC1") (pin "B10") (pinfunction "PT44A_B10") (pintype "bidirectional"))
      (node (ref "U1") (pin "54") (pinfunction "DATA_12_54") (pintype "bidirectional"))
    )
    (net (code "23") (name "D13") (class "Default")
      (node (ref "IC1") (pin "A10") (pinfunction "PT42B_A10") (pintype "bidirectional"))
      (node (ref "U1") (pin "55") (pinfunction "DATA_13_55") (pintype "bidirectional"))
    )
    (net (code "24") (name "D14") (class "Default")
      (node (ref "IC1") (pin "B9") (pinfunction "PT38A_B9") (pintype "bidirectional"))
      (node (ref "U1") (pin "56") (pinfunction "DATA_14_56") (pintype "bidirectional"))
    )
    (net (code "25") (name "D15") (class "Default")
      (node (ref "IC1") (pin "A9") (pinfunction "PT42A_A9") (pintype "bidirectional"))
      (node (ref "U1") (pin "57") (pinfunction "DATA_15_57") (pintype "bidirectional"))
    )
    (net (code "26") (name "D16") (class "Default")
      (node (ref "IC1") (pin "A8") (pinfunction "PT29B_A8") (pintype "bidirectional"))
      (node (ref "U1") (pin "60") (pinfunction "DATA_16_60") (pintype "bidirectional"))
    )
    (net (code "27") (name "D17") (class "Default")
      (node (ref "IC1") (pin "B8") (pinfunction "PT35B_B8") (pintype "bidirectional"))
      (node (ref "U1") (pin "61") (pinfunction "DATA_17_61") (pintype "bidirectional"))
    )
    (net (code "28") (name "D18") (class "Default")
      (node (ref "IC1") (pin "A7") (pinfunction "PT29A_A7") (pintype "bidirectional"))
      (node (ref "U1") (pin "62") (pinfunction "DATA_18_62") (pintype "bidirectional"))
    )
    (net (code "29") (name "D19") (class "Default")
      (node (ref "IC1") (pin "B7") (pinfunction "PT27B_B7") (pintype "bidirectional"))
      (node (ref "U1") (pin "63") (pinfunction "DATA_19_63") (pintype "bidirectional"))
    )
    (net (code "30") (name "D20") (class "Default")
      (node (ref "IC1") (pin "A6") (pinfunction "PT18B_A6") (pintype "bidirectional"))
      (node (ref "U1") (pin "64") (pinfunction "DATA_20_64") (pintype "bidirectional"))
    )
    (net (code "31") (name "D21") (class "Default")
      (node (ref "IC1") (pin "B6") (pinfunction "PT22B_B6") (pintype "bidirectional"))
      (node (ref "U1") (pin "65") (pinfunction "DATA_21_65") (pintype "bidirectional"))
    )
    (net (code "32") (name "D22") (class "Default")
      (node (ref "IC1") (pin "A5") (pinfunction "PT18A_A5") (pintype "bidirectional"))
      (node (ref "U1") (pin "66") (pinfunction "DATA_22_66") (pintype "bidirectional"))
    )
    (net (code "33") (name "D23") (class "Default")
      (node (ref "IC1") (pin "B5") (pinfunction "PT15B_B5") (pintype "bidirectional"))
      (node (ref "U1") (pin "67") (pinfunction "DATA_23_67") (pintype "bidirectional"))
    )
    (net (code "34") (name "D24") (class "Default")
      (node (ref "IC1") (pin "A4") (pinfunction "PT6B_A4") (pintype "bidirectional"))
      (node (ref "U1") (pin "69") (pinfunction "DATA_24_69") (pintype "bidirectional"))
    )
    (net (code "35") (name "D25") (class "Default")
      (node (ref "IC1") (pin "B4") (pinfunction "PT11B_B4") (pintype "bidirectional"))
      (node (ref "U1") (pin "70") (pinfunction "DATA_25_70") (pintype "bidirectional"))
    )
    (net (code "36") (name "D26") (class "Default")
      (node (ref "IC1") (pin "A3") (pinfunction "PT6A_A3") (pintype "bidirectional"))
      (node (ref "U1") (pin "71") (pinfunction "DATA_26_71") (pintype "bidirectional"))
    )
    (net (code "37") (name "D27") (class "Default")
      (node (ref "IC1") (pin "B3") (pinfunction "PT4B_B3") (pintype "bidirectional"))
      (node (ref "U1") (pin "72") (pinfunction "DATA_27_72") (pintype "bidirectional"))
    )
    (net (code "38") (name "D28") (class "Default")
      (node (ref "IC1") (pin "A2") (pinfunction "PT4A_A2") (pintype "bidirectional"))
      (node (ref "U1") (pin "73") (pinfunction "DATA_28_73") (pintype "bidirectional"))
    )
    (net (code "39") (name "D29") (class "Default")
      (node (ref "IC1") (pin "C5") (pinfunction "PT15A_C5") (pintype "bidirectional"))
      (node (ref "U1") (pin "74") (pinfunction "DATA_29_74") (pintype "bidirectional"))
    )
    (net (code "40") (name "D30") (class "Default")
      (node (ref "IC1") (pin "D4") (pinfunction "PT9B_D4") (pintype "bidirectional"))
      (node (ref "U1") (pin "75") (pinfunction "DATA_30_75") (pintype "bidirectional"))
    )
    (net (code "41") (name "D31") (class "Default")
      (node (ref "IC1") (pin "E4") (pinfunction "PT9A_E4") (pintype "bidirectional"))
      (node (ref "U1") (pin "76") (pinfunction "DATA_31_76") (pintype "bidirectional"))
    )
    (net (code "42") (name "FT6V10") (class "Default")
      (node (ref "C2") (pin "2") (pinfunction "2_2") (pintype "passive"))
      (node (ref "C22") (pin "2") (pinfunction "2_2") (pintype "passive"))
      (node (ref "C23") (pin "2") (pinfunction "2_2") (pintype "passive"))
      (node (ref "C8") (pin "2") (pinfunction "2_2") (pintype "passive"))
      (node (ref "U1") (pin "2") (pinfunction "AVDD_2") (pintype "power_in"))
      (node (ref "U1") (pin "3") (pinfunction "VD10_3") (pintype "power_in"))
      (node (ref "U1") (pin "30") (pinfunction "VD10_30") (pintype "power_in"))
      (node (ref "U1") (pin "33") (pinfunction "VD10_33") (pintype "power_in"))
      (node (ref "U1") (pin "39") (pinfunction "DV10_39") (pintype "output"))
      (node (ref "U1") (pin "48") (pinfunction "VD10_48") (pintype "power_in"))
    )
    (net (code "43") (name "GND") (class "Default")
      (node (ref "C1") (pin "2") (pinfunction "2_2") (pintype "passive"))
      (node (ref "C10") (pin "1") (pinfunction "1_1") (pintype "passive"))
      (node (ref "C11") (pin "2") (pinfunction "2_2") (pintype "passive"))
      (node (ref "C12") (pin "1") (pinfunction "1_1") (pintype "passive"))
      (node (ref "C13") (pin "2") (pinfunction "2_2") (pintype "passive"))
      (node (ref "C14") (pin "2") (pinfunction "2_2") (pintype "passive"))
      (node (ref "C15") (pin "2") (pinfunction "2_2") (pintype "passive"))
      (node (ref "C16") (pin "2") (pinfunction "2_2") (pintype "passive"))
      (node (ref "C17") (pin "2") (pinfunction "2_2") (pintype "passive"))
      (node (ref "C19") (pin "1") (pinfunction "1_1") (pintype "passive"))
      (node (ref "C2") (pin "1") (pinfunction "1_1") (pintype "passive"))
      (node (ref "C20") (pin "1") (pinfunction "1_1") (pintype "passive"))
      (node (ref "C21") (pin "2") (pinfunction "2_2") (pintype "passive"))
      (node (ref "C22") (pin "1") (pinfunction "1_1") (pintype "passive"))
      (node (ref "C23") (pin "1") (pinfunction "1_1") (pintype "passive"))
      (node (ref "C24") (pin "1") (pinfunction "1_1") (pintype "passive"))
      (node (ref "C27") (pin "2") (pinfunction "2_2") (pintype "passive"))
      (node (ref "C28") (pin "2") (pinfunction "2_2") (pintype "passive"))
      (node (ref "C29") (pin "1") (pinfunction "1_1") (pintype "passive"))
      (node (ref "C3") (pin "1") (pinfunction "1_1") (pintype "passive"))
      (node (ref "C30") (pin "1") (pinfunction "1_1") (pintype "passive"))
      (node (ref "C31") (pin "2") (pinfunction "2_2") (pintype "passive"))
      (node (ref "C32") (pin "2") (pinfunction "2_2") (pintype "passive"))
      (node (ref "C33") (pin "1") (pinfunction "1_1") (pintype "passive"))
      (node (ref "C34") (pin "2") (pinfunction "2_2") (pintype "passive"))
      (node (ref "C35") (pin "1") (pinfunction "1_1") (pintype "passive"))
      (node (ref "C36") (pin "1") (pinfunction "1_1") (pintype "passive"))
      (node (ref "C37") (pin "2") (pinfunction "2_2") (pintype "passive"))
      (node (ref "C38") (pin "2") (pinfunction "2_2") (pintype "passive"))
      (node (ref "C39") (pin "2") (pinfunction "2_2") (pintype "passive"))
      (node (ref "C4") (pin "1") (pinfunction "1_1") (pintype "passive"))
      (node (ref "C40") (pin "2") (pinfunction "2_2") (pintype "passive"))
      (node (ref "C41") (pin "2") (pinfunction "2_2") (pintype "passive"))
      (node (ref "C42") (pin "2") (pinfunction "2_2") (pintype "passive"))
      (node (ref "C5") (pin "2") (pinfunction "2_2") (pintype "passive"))
      (node (ref "C50") (pin "2") (pinfunction "2_2") (pintype "passive"))
      (node (ref "C58") (pin "2") (pinfunction "2_2") (pintype "passive"))
      (node (ref "C6") (pin "1") (pinfunction "1_1") (pintype "passive"))
      (node (ref "C7") (pin "2") (pinfunction "2_2") (pintype "passive"))
      (node (ref "C8") (pin "1") (pinfunction "1_1") (pintype "passive"))
      (node (ref "C9") (pin "1") (pinfunction "1_1") (pintype "passive"))
      (node (ref "D1") (pin "3") (pinfunction "GND_1_3") (pintype "bidirectional"))
      (node (ref "D1") (pin "8") (pinfunction "GND_2_8") (pintype "bidirectional"))
      (node (ref "D10") (pin "3") (pinfunction "GND_1_3") (pintype "bidirectional"))
      (node (ref "D10") (pin "8") (pinfunction "GND_2_8") (pintype "bidirectional"))
      (node (ref "D11") (pin "3") (pinfunction "GND_1_3") (pintype "bidirectional"))
      (node (ref "D11") (pin "8") (pinfunction "GND_2_8") (pintype "bidirectional"))
      (node (ref "D12") (pin "3") (pinfunction "GND_1_3") (pintype "bidirectional"))
      (node (ref "D12") (pin "8") (pinfunction "GND_2_8") (pintype "bidirectional"))
      (node (ref "D13") (pin "3") (pinfunction "GND_1_3") (pintype "bidirectional"))
      (node (ref "D13") (pin "8") (pinfunction "GND_2_8") (pintype "bidirectional"))
      (node (ref "D14") (pin "3") (pinfunction "GND_1_3") (pintype "bidirectional"))
      (node (ref "D14") (pin "8") (pinfunction "GND_2_8") (pintype "bidirectional"))
      (node (ref "D15") (pin "3") (pinfunction "GND_1_3") (pintype "bidirectional"))
      (node (ref "D15") (pin "8") (pinfunction "GND_2_8") (pintype "bidirectional"))
      (node (ref "D16") (pin "3") (pinfunction "GND_1_3") (pintype "bidirectional"))
      (node (ref "D16") (pin "8") (pinfunction "GND_2_8") (pintype "bidirectional"))
      (node (ref "D17") (pin "3") (pinfunction "GND_1_3") (pintype "bidirectional"))
      (node (ref "D17") (pin "8") (pinfunction "GND_2_8") (pintype "bidirectional"))
      (node (ref "IC1") (pin "A1") (pinfunction "GND_1_A1") (pintype "bidirectional"))
      (node (ref "IC1") (pin "A16") (pinfunction "GND_2_A16") (pintype "bidirectional"))
      (node (ref "IC1") (pin "D15") (pinfunction "GND_4_D15") (pintype "bidirectional"))
      (node (ref "IC1") (pin "D2") (pinfunction "GND_3_D2") (pintype "bidirectional"))
      (node (ref "IC1") (pin "F8") (pinfunction "GND_5_F8") (pintype "bidirectional"))
      (node (ref "IC1") (pin "F9") (pinfunction "GND_6_F9") (pintype "bidirectional"))
      (node (ref "IC1") (pin "G10") (pinfunction "GND_8_G10") (pintype "bidirectional"))
      (node (ref "IC1") (pin "G8") (pinfunction "GND_7_G8") (pintype "bidirectional"))
      (node (ref "IC1") (pin "H1") (pinfunction "GND_9_H1") (pintype "bidirectional"))
      (node (ref "IC1") (pin "H10") (pinfunction "GND_12_H10") (pintype "bidirectional"))
      (node (ref "IC1") (pin "H16") (pinfunction "GND_13_H16") (pintype "bidirectional"))
      (node (ref "IC1") (pin "H8") (pinfunction "GND_10_H8") (pintype "bidirectional"))
      (node (ref "IC1") (pin "H9") (pinfunction "GND_11_H9") (pintype "bidirectional"))
      (node (ref "IC1") (pin "J10") (pinfunction "GND_16_J10") (pintype "bidirectional"))
      (node (ref "IC1") (pin "J8") (pinfunction "GND_14_J8") (pintype "bidirectional"))
      (node (ref "IC1") (pin "J9") (pinfunction "GND_15_J9") (pintype "bidirectional"))
      (node (ref "IC1") (pin "K10") (pinfunction "GND_21_K10") (pintype "bidirectional"))
      (node (ref "IC1") (pin "K6") (pinfunction "GND_17_K6") (pintype "bidirectional"))
      (node (ref "IC1") (pin "K7") (pinfunction "GND_18_K7") (pintype "bidirectional"))
      (node (ref "IC1") (pin "K8") (pinfunction "GND_19_K8") (pintype "bidirectional"))
      (node (ref "IC1") (pin "K9") (pinfunction "GND_20_K9") (pintype "bidirectional"))
      (node (ref "IC1") (pin "N10") (pinfunction "CFG_0_N10") (pintype "bidirectional"))
      (node (ref "IC1") (pin "N15") (pinfunction "GND_23_N15") (pintype "bidirectional"))
      (node (ref "IC1") (pin "N2") (pinfunction "GND_22_N2") (pintype "bidirectional"))
      (node (ref "IC1") (pin "R10") (pinfunction "CFG_2_R10") (pintype "bidirectional"))
      (node (ref "IC1") (pin "T1") (pinfunction "GND_24_T1") (pintype "bidirectional"))
      (node (ref "IC1") (pin "T12") (pinfunction "GND_26_T12") (pintype "bidirectional"))
      (node (ref "IC1") (pin "T16") (pinfunction "GND_27_T16") (pintype "bidirectional"))
      (node (ref "IC1") (pin "T5") (pinfunction "GND_25_T5") (pintype "bidirectional"))
      (node (ref "IC11") (pin "2") (pinfunction "GND_2") (pintype "bidirectional"))
      (node (ref "IC3") (pin "2") (pinfunction "GND_2") (pintype "bidirectional"))
      (node (ref "J1") (pin "4") (pinfunction "4_4") (pintype "bidirectional"))
      (node (ref "J1") (pin "7") (pinfunction "7_7") (pintype "bidirectional"))
      (node (ref "J3") (pin "1") (pinfunction "1_1") (pintype "passive"))
      (node (ref "J4") (pin "3") (pinfunction "3_3") (pintype "passive"))
      (node (ref "J4") (pin "4") (pinfunction "4_4") (pintype "passive"))
      (node (ref "J5") (pin "2") (pinfunction "2_2") (pintype "passive"))
      (node (ref "J8") (pin "6") (pinfunction "6_6") (pintype "passive"))
      (node (ref "J8") (pin "7") (pinfunction "7_7") (pintype "passive"))
      (node (ref "LED1") (pin "2") (pinfunction "VSS_2") (pintype "bidirectional"))
      (node (ref "LED2") (pin "2") (pinfunction "VSS_2") (pintype "bidirectional"))
      (node (ref "LED3") (pin "2") (pinfunction "VSS_2") (pintype "bidirectional"))
      (node (ref "LED4") (pin "2") (pinfunction "VSS_2") (pintype "bidirectional"))
      (node (ref "LED5") (pin "2") (pinfunction "VSS_2") (pintype "bidirectional"))
      (node (ref "LED6") (pin "2") (pinfunction "VSS_2") (pintype "bidirectional"))
      (node (ref "LED7") (pin "2") (pinfunction "VSS_2") (pintype "bidirectional"))
      (node (ref "LED8") (pin "2") (pinfunction "VSS_2") (pintype "bidirectional"))
      (node (ref "LED9") (pin "2") (pinfunction "VSS_2") (pintype "bidirectional"))
      (node (ref "Q1") (pin "P$2") (pinfunction "GND_P$2") (pintype "power_in"))
      (node (ref "Q3") (pin "2") (pinfunction "2_2") (pintype "passive"))
      (node (ref "Q3") (pin "4") (pinfunction "4_4") (pintype "passive"))
      (node (ref "R17") (pin "1") (pinfunction "1_1") (pintype "passive"))
      (node (ref "R2") (pin "1") (pinfunction "1_1") (pintype "passive"))
      (node (ref "R23") (pin "1") (pinfunction "1_1") (pintype "passive"))
      (node (ref "R24") (pin "1") (pinfunction "1_1") (pintype "passive"))
      (node (ref "R25") (pin "1") (pinfunction "1_1") (pintype "passive"))
      (node (ref "R26") (pin "1") (pinfunction "1_1") (pintype "passive"))
      (node (ref "R28") (pin "1") (pinfunction "1_1") (pintype "passive"))
      (node (ref "R29") (pin "1") (pinfunction "1_1") (pintype "passive"))
      (node (ref "R30") (pin "1") (pinfunction "1_1") (pintype "passive"))
      (node (ref "R31") (pin "1") (pinfunction "1_1") (pintype "passive"))
      (node (ref "R32") (pin "1") (pinfunction "1_1") (pintype "passive"))
      (node (ref "R33") (pin "1") (pinfunction "1_1") (pintype "passive"))
      (node (ref "R34") (pin "1") (pinfunction "1_1") (pintype "passive"))
      (node (ref "R35") (pin "1") (pinfunction "1_1") (pintype "passive"))
      (node (ref "R8") (pin "1") (pinfunction "1_1") (pintype "passive"))
      (node (ref "RN1") (pin "1") (pinfunction "1_1") (pintype "passive"))
      (node (ref "RN1") (pin "3") (pinfunction "1_3") (pintype "passive"))
      (node (ref "RN10") (pin "1") (pinfunction "1_1") (pintype "passive"))
      (node (ref "RN10") (pin "3") (pinfunction "1_3") (pintype "passive"))
      (node (ref "RN11") (pin "1") (pinfunction "1_1") (pintype "passive"))
      (node (ref "RN11") (pin "3") (pinfunction "1_3") (pintype "passive"))
      (node (ref "RN12") (pin "1") (pinfunction "1_1") (pintype "passive"))
      (node (ref "RN12") (pin "3") (pinfunction "1_3") (pintype "passive"))
      (node (ref "RN13") (pin "1") (pinfunction "1_1") (pintype "passive"))
      (node (ref "RN13") (pin "3") (pinfunction "1_3") (pintype "passive"))
      (node (ref "RN3") (pin "1") (pinfunction "1_1") (pintype "passive"))
      (node (ref "RN3") (pin "3") (pinfunction "1_3") (pintype "passive"))
      (node (ref "RN5") (pin "1") (pinfunction "1_1") (pintype "passive"))
      (node (ref "RN5") (pin "3") (pinfunction "1_3") (pintype "passive"))
      (node (ref "RN7") (pin "1") (pinfunction "1_1") (pintype "passive"))
      (node (ref "RN7") (pin "3") (pinfunction "1_3") (pintype "passive"))
      (node (ref "U$49") (pin "A3") (pinfunction "P$3_A3") (pintype "bidirectional"))
      (node (ref "U$49") (pin "A6") (pinfunction "P$6_A6") (pintype "bidirectional"))
      (node (ref "U$49") (pin "B3") (pinfunction "P$3_B3") (pintype "bidirectional"))
      (node (ref "U$49") (pin "B6") (pinfunction "P$6_B6") (pintype "bidirectional"))
      (node (ref "U$49") (pin "C3") (pinfunction "P$3_C3") (pintype "bidirectional"))
      (node (ref "U$49") (pin "C6") (pinfunction "P$6_C6") (pintype "bidirectional"))
      (node (ref "U$49") (pin "D3") (pinfunction "P$3_D3") (pintype "bidirectional"))
      (node (ref "U$49") (pin "D6") (pinfunction "P$6_D6") (pintype "bidirectional"))
      (node (ref "U$49") (pin "S1") (pinfunction "P$1_S1") (pintype "bidirectional"))
      (node (ref "U$49") (pin "S2") (pinfunction "P$1_S2") (pintype "bidirectional"))
      (node (ref "U$49") (pin "S3") (pinfunction "P$1_S3") (pintype "bidirectional"))
      (node (ref "U$49") (pin "S4") (pinfunction "P$1_S4") (pintype "bidirectional"))
      (node (ref "U$49") (pin "S5") (pinfunction "P$1_S5") (pintype "bidirectional"))
      (node (ref "U$50") (pin "A3") (pinfunction "P$3_A3") (pintype "bidirectional"))
      (node (ref "U$50") (pin "A6") (pinfunction "P$6_A6") (pintype "bidirectional"))
      (node (ref "U$50") (pin "B3") (pinfunction "P$3_B3") (pintype "bidirectional"))
      (node (ref "U$50") (pin "B6") (pinfunction "P$6_B6") (pintype "bidirectional"))
      (node (ref "U$50") (pin "C3") (pinfunction "P$3_C3") (pintype "bidirectional"))
      (node (ref "U$50") (pin "C6") (pinfunction "P$6_C6") (pintype "bidirectional"))
      (node (ref "U$50") (pin "D3") (pinfunction "P$3_D3") (pintype "bidirectional"))
      (node (ref "U$50") (pin "D6") (pinfunction "P$6_D6") (pintype "bidirectional"))
      (node (ref "U$50") (pin "S1") (pinfunction "P$1_S1") (pintype "bidirectional"))
      (node (ref "U$50") (pin "S2") (pinfunction "P$1_S2") (pintype "bidirectional"))
      (node (ref "U$50") (pin "S3") (pinfunction "P$1_S3") (pintype "bidirectional"))
      (node (ref "U$50") (pin "S4") (pinfunction "P$1_S4") (pintype "bidirectional"))
      (node (ref "U$50") (pin "S5") (pinfunction "P$1_S5") (pintype "bidirectional"))
      (node (ref "U1") (pin "1") (pinfunction "GND_1") (pintype "power_in"))
      (node (ref "U1") (pin "26") (pinfunction "GND_26") (pintype "power_in"))
      (node (ref "U1") (pin "29") (pinfunction "GND_29") (pintype "power_in"))
      (node (ref "U1") (pin "36") (pinfunction "GND_36") (pintype "power_in"))
      (node (ref "U1") (pin "77") (pinfunction "EXP_77") (pintype "power_in"))
      (node (ref "U3") (pin "4") (pinfunction "GND_4") (pintype "power_in"))
      (node (ref "U4") (pin "2") (pinfunction "GND_2") (pintype "power_in"))
      (node (ref "U5") (pin "2") (pinfunction "GND_2") (pintype "power_in"))
      (node (ref "U6") (pin "2") (pinfunction "GND_2") (pintype "power_in"))
      (node (ref "U7") (pin "2") (pinfunction "GND_2") (pintype "power_in"))
      (node (ref "U8") (pin "4") (pinfunction "GND_4") (pintype "power_in"))
      (node (ref "X1") (pin "5") (pinfunction "5_5") (pintype "passive"))
    )
    (net (code "44") (name "GPIO0") (class "Default")
      (node (ref "J4") (pin "6") (pinfunction "6_6") (pintype "passive"))
      (node (ref "R21") (pin "1") (pinfunction "1_1") (pintype "passive"))
      (node (ref "U1") (pin "17") (pinfunction "GPIO0_17") (pintype "bidirectional"))
    )
    (net (code "45") (name "GPIO1") (class "Default")
      (node (ref "J4") (pin "8") (pinfunction "8_8") (pintype "passive"))
      (node (ref "R23") (pin "2") (pinfunction "2_2") (pintype "passive"))
      (node (ref "U1") (pin "18") (pinfunction "GPIO1_18") (pintype "bidirectional"))
      (node (ref "U8") (pin "3") (pinfunction "IN_3") (pintype "input"))
    )
    (net (code "46") (name "INITN") (class "Default")
      (node (ref "IC1") (pin "T9") (pinfunction "INITN_T9") (pintype "bidirectional"))
      (node (ref "J2") (pin "2") (pinfunction "2_2") (pintype "passive"))
      (node (ref "R1") (pin "1") (pinfunction "1_1") (pintype "passive"))
    )
    (net (code "47") (name "JTAG_TCK") (class "Default")
      (node (ref "IC1") (pin "T10") (pinfunction "TCK_T10") (pintype "bidirectional"))
      (node (ref "J3") (pin "2") (pinfunction "2_2") (pintype "passive"))
      (node (ref "R2") (pin "2") (pinfunction "2_2") (pintype "passive"))
      (node (ref "X1") (pin "4") (pinfunction "4_4") (pintype "passive"))
    )
    (net (code "48") (name "JTAG_TDI") (class "Default")
      (node (ref "IC1") (pin "R11") (pinfunction "TDI_R11") (pintype "bidirectional"))
      (node (ref "J3") (pin "3") (pinfunction "3_3") (pintype "passive"))
      (node (ref "X1") (pin "3") (pinfunction "3_3") (pintype "passive"))
    )
    (net (code "49") (name "JTAG_TDO") (class "Default")
      (node (ref "IC1") (pin "M10") (pinfunction "TDO_M10") (pintype "bidirectional"))
      (node (ref "J3") (pin "4") (pinfunction "4_4") (pintype "passive"))
      (node (ref "X1") (pin "2") (pinfunction "2_2") (pintype "passive"))
    )
    (net (code "50") (name "JTAG_TMS") (class "Default")
      (node (ref "IC1") (pin "T11") (pinfunction "TMS_T11") (pintype "bidirectional"))
      (node (ref "J3") (pin "5") (pinfunction "5_5") (pintype "passive"))
      (node (ref "X1") (pin "1") (pinfunction "1_1") (pintype "passive"))
    )
    (net (code "51") (name "LEDCTRL") (class "Default")
      (node (ref "J5") (pin "1") (pinfunction "1_1") (pintype "passive"))
      (node (ref "LED4") (pin "4") (pinfunction "DIN_4") (pintype "bidirectional"))
      (node (ref "R27") (pin "2") (pinfunction "2_2") (pintype "passive"))
    )
    (net (code "52") (name "MCLK") (class "Default")
      (node (ref "IC1") (pin "K2") (pinfunction "PL23D_K2") (pintype "bidirectional"))
      (node (ref "Q1") (pin "P$3") (pinfunction "FO_P$3") (pintype "output"))
    )
    (net (code "53") (name "Net-(D2-PadC)") (class "Default")
      (node (ref "D2") (pin "C") (pinfunction "C_C") (pintype "passive"))
      (node (ref "R12") (pin "1") (pinfunction "1_1") (pintype "passive"))
    )
    (net (code "54") (name "Net-(D3-PadC)") (class "Default")
      (node (ref "D3") (pin "C") (pinfunction "C_C") (pintype "passive"))
      (node (ref "R11") (pin "1") (pinfunction "1_1") (pintype "passive"))
    )
    (net (code "55") (name "Net-(D4-PadC)") (class "Default")
      (node (ref "D4") (pin "C") (pinfunction "C_C") (pintype "passive"))
      (node (ref "R13") (pin "1") (pinfunction "1_1") (pintype "passive"))
    )
    (net (code "56") (name "Net-(D5-PadC)") (class "Default")
      (node (ref "D5") (pin "C") (pinfunction "C_C") (pintype "passive"))
      (node (ref "R14") (pin "1") (pinfunction "1_1") (pintype "passive"))
    )
    (net (code "57") (name "Net-(D6-PadC)") (class "Default")
      (node (ref "D6") (pin "C") (pinfunction "C_C") (pintype "passive"))
      (node (ref "R15") (pin "1") (pinfunction "1_1") (pintype "passive"))
    )
    (net (code "58") (name "Net-(D7-PadC)") (class "Default")
      (node (ref "D7") (pin "C") (pinfunction "C_C") (pintype "passive"))
      (node (ref "R16") (pin "1") (pinfunction "1_1") (pintype "passive"))
    )
    (net (code "59") (name "Net-(D8-PadC)") (class "Default")
      (node (ref "D8") (pin "C") (pinfunction "C_C") (pintype "passive"))
      (node (ref "R18") (pin "1") (pinfunction "1_1") (pintype "passive"))
    )
    (net (code "60") (name "Net-(D9-PadC)") (class "Default")
      (node (ref "D9") (pin "C") (pinfunction "C_C") (pintype "passive"))
      (node (ref "R20") (pin "1") (pinfunction "1_1") (pintype "passive"))
    )
    (net (code "61") (name "Net-(IC3-LX)") (class "Default")
      (node (ref "IC3") (pin "5") (pinfunction "LX_5") (pintype "bidirectional"))
      (node (ref "L1") (pin "2") (pinfunction "2_2") (pintype "passive"))
    )
    (net (code "62") (name "Net-(IC11-VBUS)") (class "Default")
      (node (ref "C12") (pin "2") (pinfunction "2_2") (pintype "passive"))
      (node (ref "IC11") (pin "5") (pinfunction "VBUS_5") (pintype "bidirectional"))
      (node (ref "JP3") (pin "1") (pinfunction "1_1") (pintype "passive"))
    )
    (net (code "63") (name "Net-(J1-Pad1)") (class "Default")
      (node (ref "J1") (pin "1") (pinfunction "1_1") (pintype "bidirectional"))
      (node (ref "R5") (pin "2") (pinfunction "2_2") (pintype "passive"))
    )
    (net (code "64") (name "Net-(LED1-DIN)") (class "Default")
      (node (ref "LED1") (pin "4") (pinfunction "DIN_4") (pintype "bidirectional"))
      (node (ref "LED2") (pin "1") (pinfunction "DOUT_1") (pintype "bidirectional"))
    )
    (net (code "65") (name "Net-(LED1-DOUT)") (class "Default")
      (node (ref "LED1") (pin "1") (pinfunction "DOUT_1") (pintype "bidirectional"))
      (node (ref "LED5") (pin "4") (pinfunction "DIN_4") (pintype "bidirectional"))
    )
    (net (code "66") (name "Net-(LED2-DIN)") (class "Default")
      (node (ref "LED2") (pin "4") (pinfunction "DIN_4") (pintype "bidirectional"))
      (node (ref "LED3") (pin "1") (pinfunction "DOUT_1") (pintype "bidirectional"))
    )
    (net (code "67") (name "Net-(LED3-DIN)") (class "Default")
      (node (ref "LED3") (pin "4") (pinfunction "DIN_4") (pintype "bidirectional"))
      (node (ref "LED4") (pin "1") (pinfunction "DOUT_1") (pintype "bidirectional"))
    )
    (net (code "68") (name "Net-(LED5-DOUT)") (class "Default")
      (node (ref "LED5") (pin "1") (pinfunction "DOUT_1") (pintype "bidirectional"))
      (node (ref "LED9") (pin "4") (pinfunction "DIN_4") (pintype "bidirectional"))
    )
    (net (code "69") (name "Net-(LED6-DIN)") (class "Default")
      (node (ref "LED6") (pin "4") (pinfunction "DIN_4") (pintype "bidirectional"))
      (node (ref "LED7") (pin "1") (pinfunction "DOUT_1") (pintype "bidirectional"))
    )
    (net (code "70") (name "Net-(LED7-DIN)") (class "Default")
      (node (ref "LED7") (pin "4") (pinfunction "DIN_4") (pintype "bidirectional"))
      (node (ref "LED8") (pin "1") (pinfunction "DOUT_1") (pintype "bidirectional"))
    )
    (net (code "71") (name "Net-(LED8-DIN)") (class "Default")
      (node (ref "LED8") (pin "4") (pinfunction "DIN_4") (pintype "bidirectional"))
      (node (ref "LED9") (pin "1") (pinfunction "DOUT_1") (pintype "bidirectional"))
    )
    (net (code "72") (name "Net-(Q4-D-Pad5)") (class "Default")
      (node (ref "Q4") (pin "5") (pinfunction "D_5") (pintype "passive"))
      (node (ref "Q4") (pin "6") (pinfunction "D_6") (pintype "passive"))
      (node (ref "Q4") (pin "7") (pinfunction "D_7") (pintype "passive"))
      (node (ref "Q4") (pin "8") (pinfunction "D_8") (pintype "passive"))
      (node (ref "R22") (pin "2") (pinfunction "2_2") (pintype "passive"))
    )
    (net (code "73") (name "Net-(Q4-G)") (class "Default")
      (node (ref "Q4") (pin "4") (pinfunction "G_4") (pintype "passive"))
      (node (ref "U8") (pin "5") (pinfunction "~{OUT}_5") (pintype "output"))
    )
    (net (code "74") (name "Net-(R5-Pad1)") (class "Default")
      (node (ref "R5") (pin "1") (pinfunction "1_1") (pintype "passive"))
      (node (ref "R6") (pin "2") (pinfunction "2_2") (pintype "passive"))
    )
    (net (code "75") (name "Net-(U$49A-P$1)") (class "Default")
      (node (ref "R28") (pin "2") (pinfunction "2_2") (pintype "passive"))
      (node (ref "U$49") (pin "A1") (pinfunction "P$1_A1") (pintype "bidirectional"))
    )
    (net (code "76") (name "Net-(U$49A-P$2)") (class "Default")
      (node (ref "R11") (pin "2") (pinfunction "2_2") (pintype "passive"))
      (node (ref "U$49") (pin "A2") (pinfunction "P$2_A2") (pintype "bidirectional"))
    )
    (net (code "77") (name "Net-(U$49B-P$1)") (class "Default")
      (node (ref "R29") (pin "2") (pinfunction "2_2") (pintype "passive"))
      (node (ref "U$49") (pin "B1") (pinfunction "P$1_B1") (pintype "bidirectional"))
    )
    (net (code "78") (name "Net-(U$49B-P$2)") (class "Default")
      (node (ref "R12") (pin "2") (pinfunction "2_2") (pintype "passive"))
      (node (ref "U$49") (pin "B2") (pinfunction "P$2_B2") (pintype "bidirectional"))
    )
    (net (code "79") (name "Net-(U$49C-P$1)") (class "Default")
      (node (ref "R30") (pin "2") (pinfunction "2_2") (pintype "passive"))
      (node (ref "U$49") (pin "C1") (pinfunction "P$1_C1") (pintype "bidirectional"))
    )
    (net (code "80") (name "Net-(U$49C-P$2)") (class "Default")
      (node (ref "R13") (pin "2") (pinfunction "2_2") (pintype "passive"))
      (node (ref "U$49") (pin "C2") (pinfunction "P$2_C2") (pintype "bidirectional"))
    )
    (net (code "81") (name "Net-(U$49D-P$1)") (class "Default")
      (node (ref "R31") (pin "2") (pinfunction "2_2") (pintype "passive"))
      (node (ref "U$49") (pin "D1") (pinfunction "P$1_D1") (pintype "bidirectional"))
    )
    (net (code "82") (name "Net-(U$49D-P$2)") (class "Default")
      (node (ref "R14") (pin "2") (pinfunction "2_2") (pintype "passive"))
      (node (ref "U$49") (pin "D2") (pinfunction "P$2_D2") (pintype "bidirectional"))
    )
    (net (code "83") (name "Net-(U$50A-P$1)") (class "Default")
      (node (ref "R35") (pin "2") (pinfunction "2_2") (pintype "passive"))
      (node (ref "U$50") (pin "A1") (pinfunction "P$1_A1") (pintype "bidirectional"))
    )
    (net (code "84") (name "Net-(U$50A-P$2)") (class "Default")
      (node (ref "R15") (pin "2") (pinfunction "2_2") (pintype "passive"))
      (node (ref "U$50") (pin "A2") (pinfunction "P$2_A2") (pintype "bidirectional"))
    )
    (net (code "85") (name "Net-(U$50B-P$1)") (class "Default")
      (node (ref "R34") (pin "2") (pinfunction "2_2") (pintype "passive"))
      (node (ref "U$50") (pin "B1") (pinfunction "P$1_B1") (pintype "bidirectional"))
    )
    (net (code "86") (name "Net-(U$50B-P$2)") (class "Default")
      (node (ref "R16") (pin "2") (pinfunction "2_2") (pintype "passive"))
      (node (ref "U$50") (pin "B2") (pinfunction "P$2_B2") (pintype "bidirectional"))
    )
    (net (code "87") (name "Net-(U$50C-P$1)") (class "Default")
      (node (ref "R33") (pin "2") (pinfunction "2_2") (pintype "passive"))
      (node (ref "U$50") (pin "C1") (pinfunction "P$1_C1") (pintype "bidirectional"))
    )
    (net (code "88") (name "Net-(U$50C-P$2)") (class "Default")
      (node (ref "R18") (pin "2") (pinfunction "2_2") (pintype "passive"))
      (node (ref "U$50") (pin "C2") (pinfunction "P$2_C2") (pintype "bidirectional"))
    )
    (net (code "89") (name "Net-(U$50D-P$1)") (class "Default")
      (node (ref "R32") (pin "2") (pinfunction "2_2") (pintype "passive"))
      (node (ref "U$50") (pin "D1") (pinfunction "P$1_D1") (pintype "bidirectional"))
    )
    (net (code "90") (name "Net-(U$50D-P$2)") (class "Default")
      (node (ref "R20") (pin "2") (pinfunction "2_2") (pintype "passive"))
      (node (ref "U$50") (pin "D2") (pinfunction "P$2_D2") (pintype "bidirectional"))
    )
    (net (code "91") (name "OEN") (class "Default")
      (node (ref "IC1") (pin "K1") (pinfunction "PL23C_K1") (pintype "bidirectional"))
      (node (ref "RN8") (pin "1") (pinfunction "1_1") (pintype "passive"))
      (node (ref "U1") (pin "13") (pinfunction "OE_N_13") (pintype "input"))
    )
    (net (code "92") (name "PB4A") (class "Default")
      (node (ref "IC1") (pin "T6") (pinfunction "PB4A_T6") (pintype "bidirectional"))
      (node (ref "JP1") (pin "2") (pinfunction "2_2") (pintype "passive"))
    )
    (net (code "93") (name "PB4B") (class "Default")
      (node (ref "IC1") (pin "R6") (pinfunction "PB4B_R6") (pintype "bidirectional"))
    )
    (net (code "94") (name "PCSN") (class "Default")
      (node (ref "IC1") (pin "N8") (pinfunction "PB15A_N8") (pintype "bidirectional"))
      (node (ref "R10") (pin "2") (pinfunction "2_2") (pintype "passive"))
      (node (ref "U3") (pin "1") (pinfunction "CS_1") (pintype "bidirectional"))
    )
    (net (code "95") (name "PDONE") (class "Default")
      (node (ref "IC1") (pin "P9") (pinfunction "DONE_P9") (pintype "bidirectional"))
    )
    (net (code "96") (name "PL26A") (class "Default")
      (node (ref "IC1") (pin "L1") (pinfunction "PL26A_L1") (pintype "bidirectional"))
      (node (ref "RN9") (pin "3") (pinfunction "1_3") (pintype "passive"))
    )
    (net (code "97") (name "PL26B") (class "Default")
      (node (ref "IC1") (pin "L2") (pinfunction "PL26B_L2") (pintype "bidirectional"))
      (node (ref "RN9") (pin "4") (pinfunction "1_4") (pintype "passive"))
    )
    (net (code "98") (name "PL26C") (class "Default")
      (node (ref "IC1") (pin "M1") (pinfunction "PL26C_M1") (pintype "bidirectional"))
      (node (ref "RN9") (pin "1") (pinfunction "1_1") (pintype "passive"))
    )
    (net (code "99") (name "PL26D") (class "Default")
      (node (ref "IC1") (pin "M2") (pinfunction "PL26D_M2") (pintype "bidirectional"))
      (node (ref "RN9") (pin "2") (pinfunction "1_2") (pintype "passive"))
    )
    (net (code "100") (name "PL32A") (class "Default")
      (node (ref "IC1") (pin "N1") (pinfunction "PL32A_N1") (pintype "bidirectional"))
      (node (ref "RN6") (pin "4") (pinfunction "1_4") (pintype "passive"))
    )
    (net (code "101") (name "PL32B") (class "Default")
      (node (ref "IC1") (pin "P2") (pinfunction "PL32B_P2") (pintype "bidirectional"))
      (node (ref "RN6") (pin "3") (pinfunction "1_3") (pintype "passive"))
    )
    (net (code "102") (name "PL35A") (class "Default")
      (node (ref "IC1") (pin "P1") (pinfunction "PL35A_P1") (pintype "bidirectional"))
      (node (ref "RN6") (pin "2") (pinfunction "1_2") (pintype "passive"))
    )
    (net (code "103") (name "PL35B") (class "Default")
      (node (ref "IC1") (pin "R1") (pinfunction "PL35B_R1") (pintype "bidirectional"))
      (node (ref "RN6") (pin "1") (pinfunction "1_1") (pintype "passive"))
    )
    (net (code "104") (name "PL38A") (class "Default")
      (node (ref "IC1") (pin "N4") (pinfunction "PL38A_N4") (pintype "bidirectional"))
    )
    (net (code "105") (name "PL38B") (class "Default")
      (node (ref "IC1") (pin "P3") (pinfunction "PL38B_P3") (pintype "bidirectional"))
    )
    (net (code "106") (name "PL38C") (class "Default")
      (node (ref "IC1") (pin "R2") (pinfunction "PL38C_R2") (pintype "bidirectional"))
      (node (ref "RN4") (pin "3") (pinfunction "1_3") (pintype "passive"))
    )
    (net (code "107") (name "PL38D") (class "Default")
      (node (ref "IC1") (pin "T2") (pinfunction "PL38D_T2") (pintype "bidirectional"))
      (node (ref "RN4") (pin "4") (pinfunction "1_4") (pintype "passive"))
    )
    (net (code "108") (name "PL41A") (class "Default")
      (node (ref "IC1") (pin "P4") (pinfunction "PL41A_P4") (pintype "bidirectional"))
      (node (ref "RN2") (pin "3") (pinfunction "1_3") (pintype "passive"))
    )
    (net (code "109") (name "PL41B") (class "Default")
      (node (ref "IC1") (pin "R3") (pinfunction "PL41B_R3") (pintype "bidirectional"))
      (node (ref "RN2") (pin "4") (pinfunction "1_4") (pintype "passive"))
    )
    (net (code "110") (name "PL41C") (class "Default")
      (node (ref "IC1") (pin "R4") (pinfunction "PL41C_R4") (pintype "bidirectional"))
      (node (ref "RN4") (pin "2") (pinfunction "1_2") (pintype "passive"))
    )
    (net (code "111") (name "PL41D") (class "Default")
      (node (ref "IC1") (pin "T3") (pinfunction "PL41D_T3") (pintype "bidirectional"))
      (node (ref "RN4") (pin "1") (pinfunction "1_1") (pintype "passive"))
    )
    (net (code "112") (name "PL44A") (class "Default")
      (node (ref "IC1") (pin "R5") (pinfunction "PL44A_R5") (pintype "bidirectional"))
      (node (ref "RN2") (pin "1") (pinfunction "1_1") (pintype "passive"))
    )
    (net (code "113") (name "PL44B") (class "Default")
      (node (ref "IC1") (pin "T4") (pinfunction "PL44B_T4") (pintype "bidirectional"))
      (node (ref "RN2") (pin "2") (pinfunction "1_2") (pintype "passive"))
    )
    (net (code "114") (name "PMISO") (class "Default")
      (node (ref "IC1") (pin "T7") (pinfunction "PB11A_T7") (pintype "bidirectional"))
      (node (ref "U3") (pin "2") (pinfunction "MISO_2") (pintype "bidirectional"))
    )
    (net (code "115") (name "PMOSI") (class "Default")
      (node (ref "IC1") (pin "T8") (pinfunction "PB11B_T8") (pintype "bidirectional"))
      (node (ref "U3") (pin "5") (pinfunction "MOSI_5") (pintype "bidirectional"))
    )
    (net (code "116") (name "PR20A") (class "Default")
      (node (ref "IC1") (pin "G16") (pinfunction "PR20A_G16") (pintype "bidirectional"))
      (node (ref "RN15") (pin "1") (pinfunction "1_1") (pintype "passive"))
    )
    (net (code "117") (name "PR20B") (class "Default")
      (node (ref "IC1") (pin "H15") (pinfunction "PR20B_H15") (pintype "bidirectional"))
      (node (ref "RN15") (pin "2") (pinfunction "1_2") (pintype "passive"))
    )
    (net (code "118") (name "PR23A") (class "Default")
      (node (ref "IC1") (pin "J16") (pinfunction "PR23A_J16") (pintype "bidirectional"))
      (node (ref "RN15") (pin "4") (pinfunction "1_4") (pintype "passive"))
    )
    (net (code "119") (name "PR23B") (class "Default")
      (node (ref "IC1") (pin "J15") (pinfunction "PR23B_J15") (pintype "bidirectional"))
      (node (ref "RN15") (pin "3") (pinfunction "1_3") (pintype "passive"))
    )
    (net (code "120") (name "PR26A") (class "Default")
      (node (ref "IC1") (pin "L16") (pinfunction "PR26A_L16") (pintype "bidirectional"))
      (node (ref "RN17") (pin "2") (pinfunction "1_2") (pintype "passive"))
    )
    (net (code "121") (name "PR26B") (class "Default")
      (node (ref "IC1") (pin "L15") (pinfunction "PR26B_L15") (pintype "bidirectional"))
      (node (ref "RN17") (pin "1") (pinfunction "1_1") (pintype "passive"))
    )
    (net (code "122") (name "PR32A") (class "Default")
      (node (ref "IC1") (pin "N16") (pinfunction "PR32A_N16") (pintype "bidirectional"))
      (node (ref "RN17") (pin "3") (pinfunction "1_3") (pintype "passive"))
    )
    (net (code "123") (name "PR32B") (class "Default")
      (node (ref "IC1") (pin "P15") (pinfunction "PR32B_P15") (pintype "bidirectional"))
      (node (ref "RN17") (pin "4") (pinfunction "1_4") (pintype "passive"))
    )
    (net (code "124") (name "PR35A") (class "Default")
      (node (ref "IC1") (pin "P16") (pinfunction "PR35A_P16") (pintype "bidirectional"))
      (node (ref "RN19") (pin "1") (pinfunction "1_1") (pintype "passive"))
    )
    (net (code "125") (name "PR35B") (class "Default")
      (node (ref "IC1") (pin "R16") (pinfunction "PR35B_R16") (pintype "bidirectional"))
      (node (ref "RN19") (pin "2") (pinfunction "1_2") (pintype "passive"))
    )
    (net (code "126") (name "PR38C") (class "Default")
      (node (ref "IC1") (pin "R15") (pinfunction "PR38C_R15") (pintype "bidirectional"))
      (node (ref "RN19") (pin "3") (pinfunction "1_3") (pintype "passive"))
    )
    (net (code "127") (name "PR38D") (class "Default")
      (node (ref "IC1") (pin "T15") (pinfunction "PR38D_T15") (pintype "bidirectional"))
      (node (ref "RN19") (pin "4") (pinfunction "1_4") (pintype "passive"))
    )
    (net (code "128") (name "PR41C") (class "Default")
      (node (ref "IC1") (pin "R13") (pinfunction "PR41C_R13") (pintype "bidirectional"))
      (node (ref "RN21") (pin "2") (pinfunction "1_2") (pintype "passive"))
    )
    (net (code "129") (name "PR41D") (class "Default")
      (node (ref "IC1") (pin "T14") (pinfunction "PR41D_T14") (pintype "bidirectional"))
      (node (ref "RN21") (pin "1") (pinfunction "1_1") (pintype "passive"))
    )
    (net (code "130") (name "PR44A") (class "Default")
      (node (ref "IC1") (pin "R12") (pinfunction "PR44A_R12") (pintype "bidirectional"))
      (node (ref "RN21") (pin "4") (pinfunction "1_4") (pintype "passive"))
    )
    (net (code "131") (name "PR44B") (class "Default")
      (node (ref "IC1") (pin "T13") (pinfunction "PR44B_T13") (pintype "bidirectional"))
      (node (ref "RN21") (pin "3") (pinfunction "1_3") (pintype "passive"))
    )
    (net (code "132") (name "PROGRAMN") (class "Default")
      (node (ref "C13") (pin "1") (pinfunction "1_1") (pintype "passive"))
      (node (ref "IC1") (pin "R9") (pinfunction "PROGRAMN_R9") (pintype "bidirectional"))
      (node (ref "J2") (pin "1") (pinfunction "1_1") (pintype "passive"))
      (node (ref "R21") (pin "2") (pinfunction "2_2") (pintype "passive"))
      (node (ref "R4") (pin "2") (pinfunction "2_2") (pintype "passive"))
      (node (ref "R9") (pin "2") (pinfunction "2_2") (pintype "passive"))
    )
    (net (code "133") (name "PSCK") (class "Default")
      (node (ref "IC1") (pin "N9") (pinfunction "CCLK_N9") (pintype "bidirectional"))
      (node (ref "JP1") (pin "1") (pinfunction "1_1") (pintype "passive"))
      (node (ref "R7") (pin "2") (pinfunction "2_2") (pintype "passive"))
      (node (ref "U3") (pin "6") (pinfunction "SCK_6") (pintype "bidirectional"))
    )
    (net (code "134") (name "QB2") (class "Default")
      (node (ref "IC1") (pin "B2") (pinfunction "PL2B_B2") (pintype "bidirectional"))
      (node (ref "R27") (pin "1") (pinfunction "1_1") (pintype "passive"))
    )
    (net (code "135") (name "QC16") (class "Default")
      (node (ref "IC1") (pin "C16") (pinfunction "PR5A_C16") (pintype "bidirectional"))
      (node (ref "J8") (pin "3") (pinfunction "3_3") (pintype "passive"))
    )
    (net (code "136") (name "QD16") (class "Default")
      (node (ref "IC1") (pin "D16") (pinfunction "PR8A_D16") (pintype "bidirectional"))
      (node (ref "J8") (pin "4") (pinfunction "4_4") (pintype "passive"))
    )
    (net (code "137") (name "QE16") (class "Default")
      (node (ref "IC1") (pin "E16") (pinfunction "PR11D_E16") (pintype "bidirectional"))
    )
    (net (code "138") (name "QF16") (class "Default")
      (node (ref "IC1") (pin "F16") (pinfunction "PR14A_F16") (pintype "bidirectional"))
      (node (ref "J8") (pin "5") (pinfunction "5_5") (pintype "passive"))
    )
    (net (code "139") (name "QK16") (class "Default")
      (node (ref "IC1") (pin "K16") (pinfunction "PR23C_K16") (pintype "bidirectional"))
      (node (ref "R9") (pin "1") (pinfunction "1_1") (pintype "passive"))
    )
    (net (code "140") (name "QL3") (class "Default")
      (node (ref "IC1") (pin "L3") (pinfunction "PL32C_L3") (pintype "bidirectional"))
    )
    (net (code "141") (name "QM16") (class "Default")
      (node (ref "IC1") (pin "M16") (pinfunction "PR26C_M16") (pintype "bidirectional"))
    )
    (net (code "142") (name "QR2A") (class "Default")
      (node (ref "IC1") (pin "B16") (pinfunction "PR2A_B16") (pintype "bidirectional"))
      (node (ref "J8") (pin "1") (pinfunction "1_1") (pintype "passive"))
    )
    (net (code "143") (name "QR2B") (class "Default")
      (node (ref "IC1") (pin "B15") (pinfunction "PR2B_B15") (pintype "bidirectional"))
      (node (ref "J8") (pin "2") (pinfunction "2_2") (pintype "passive"))
    )
    (net (code "144") (name "RDN") (class "Default")
      (node (ref "IC1") (pin "J1") (pinfunction "PL23A_J1") (pintype "bidirectional"))
      (node (ref "RN8") (pin "2") (pinfunction "1_2") (pintype "passive"))
      (node (ref "U1") (pin "12") (pinfunction "RD_N_12") (pintype "input"))
    )
    (net (code "145") (name "RESET_N") (class "Default")
      (node (ref "C33") (pin "2") (pinfunction "2_2") (pintype "passive"))
      (node (ref "J4") (pin "5") (pinfunction "5_5") (pintype "passive"))
      (node (ref "R19") (pin "2") (pinfunction "2_2") (pintype "passive"))
      (node (ref "U1") (pin "15") (pinfunction "RESET_N_15") (pintype "input"))
    )
    (net (code "146") (name "RXFN") (class "Default")
      (node (ref "IC1") (pin "G2") (pinfunction "PL14B_G2") (pintype "bidirectional"))
      (node (ref "U1") (pin "9") (pinfunction "RXF_N_9") (pintype "output"))
    )
    (net (code "147") (name "SIWUN") (class "Default")
      (node (ref "RN8") (pin "4") (pinfunction "1_4") (pintype "passive"))
      (node (ref "U1") (pin "10") (pinfunction "SIWU_N_10") (pintype "input"))
    )
    (net (code "148") (name "SSRX+") (class "Default")
      (node (ref "D1") (pin "5") (pinfunction "CH4_5") (pintype "bidirectional"))
      (node (ref "D1") (pin "6") (pinfunction "N.C._1_6") (pintype "bidirectional"))
      (node (ref "J1") (pin "9") (pinfunction "9_9") (pintype "bidirectional"))
      (node (ref "U1") (pin "35") (pinfunction "RIDP_35") (pintype "input"))
    )
    (net (code "149") (name "SSRX-") (class "Default")
      (node (ref "D1") (pin "4") (pinfunction "CH3_4") (pintype "bidirectional"))
      (node (ref "D1") (pin "7") (pinfunction "N.C._2_7") (pintype "bidirectional"))
      (node (ref "J1") (pin "8") (pinfunction "8_8") (pintype "bidirectional"))
      (node (ref "U1") (pin "34") (pinfunction "RIDN_34") (pintype "input"))
    )
    (net (code "150") (name "SSTX+") (class "Default")
      (node (ref "C26") (pin "2") (pinfunction "2_2") (pintype "passive"))
      (node (ref "J1") (pin "6") (pinfunction "6_6") (pintype "bidirectional"))
    )
    (net (code "151") (name "SSTX-") (class "Default")
      (node (ref "C25") (pin "2") (pinfunction "2_2") (pintype "passive"))
      (node (ref "J1") (pin "5") (pinfunction "5_5") (pintype "bidirectional"))
    )
    (net (code "152") (name "SSTXI+") (class "Default")
      (node (ref "C26") (pin "1") (pinfunction "1_1") (pintype "passive"))
      (node (ref "D1") (pin "2") (pinfunction "CH2_2") (pintype "bidirectional"))
      (node (ref "D1") (pin "9") (pinfunction "N.C._3_9") (pintype "bidirectional"))
      (node (ref "U1") (pin "32") (pinfunction "T0DP_32") (pintype "output"))
    )
    (net (code "153") (name "SSTXI-") (class "Default")
      (node (ref "C25") (pin "1") (pinfunction "1_1") (pintype "passive"))
      (node (ref "D1") (pin "1") (pinfunction "CH1_1") (pintype "bidirectional"))
      (node (ref "D1") (pin "10") (pinfunction "N.C._4_10") (pintype "bidirectional"))
      (node (ref "U1") (pin "31") (pinfunction "T0DN_31") (pintype "output"))
    )
    (net (code "154") (name "TA1") (class "Default")
      (node (ref "D10") (pin "1") (pinfunction "CH1_1") (pintype "bidirectional"))
      (node (ref "D10") (pin "10") (pinfunction "N.C._4_10") (pintype "bidirectional"))
      (node (ref "R48") (pin "1") (pinfunction "1_1") (pintype "passive"))
      (node (ref "RN1") (pin "5") (pinfunction "2_5") (pintype "passive"))
      (node (ref "RN2") (pin "8") (pinfunction "2_8") (pintype "passive"))
      (node (ref "U$49") (pin "A4") (pinfunction "P$4_A4") (pintype "bidirectional"))
    )
    (net (code "155") (name "TA2") (class "Default")
      (node (ref "D10") (pin "2") (pinfunction "CH2_2") (pintype "bidirectional"))
      (node (ref "D10") (pin "9") (pinfunction "N.C._3_9") (pintype "bidirectional"))
      (node (ref "R48") (pin "2") (pinfunction "2_2") (pintype "passive"))
      (node (ref "RN1") (pin "6") (pinfunction "2_6") (pintype "passive"))
      (node (ref "RN2") (pin "7") (pinfunction "2_7") (pintype "passive"))
      (node (ref "U$49") (pin "A5") (pinfunction "P$5_A5") (pintype "bidirectional"))
    )
    (net (code "156") (name "TA3") (class "Default")
      (node (ref "D10") (pin "4") (pinfunction "CH3_4") (pintype "bidirectional"))
      (node (ref "D10") (pin "7") (pinfunction "N.C._2_7") (pintype "bidirectional"))
      (node (ref "R47") (pin "1") (pinfunction "1_1") (pintype "passive"))
      (node (ref "RN1") (pin "7") (pinfunction "2_7") (pintype "passive"))
      (node (ref "RN2") (pin "6") (pinfunction "2_6") (pintype "passive"))
      (node (ref "U$49") (pin "A7") (pinfunction "P$7_A7") (pintype "bidirectional"))
    )
    (net (code "157") (name "TA4") (class "Default")
      (node (ref "D10") (pin "5") (pinfunction "CH4_5") (pintype "bidirectional"))
      (node (ref "D10") (pin "6") (pinfunction "N.C._1_6") (pintype "bidirectional"))
      (node (ref "R47") (pin "2") (pinfunction "2_2") (pintype "passive"))
      (node (ref "RN1") (pin "8") (pinfunction "2_8") (pintype "passive"))
      (node (ref "RN2") (pin "5") (pinfunction "2_5") (pintype "passive"))
      (node (ref "U$49") (pin "A8") (pinfunction "P$8_A8") (pintype "bidirectional"))
    )
    (net (code "158") (name "TB1") (class "Default")
      (node (ref "D11") (pin "1") (pinfunction "CH1_1") (pintype "bidirectional"))
      (node (ref "D11") (pin "10") (pinfunction "N.C._4_10") (pintype "bidirectional"))
      (node (ref "R46") (pin "2") (pinfunction "2_2") (pintype "passive"))
      (node (ref "RN3") (pin "5") (pinfunction "2_5") (pintype "passive"))
      (node (ref "RN4") (pin "8") (pinfunction "2_8") (pintype "passive"))
      (node (ref "U$49") (pin "B4") (pinfunction "P$4_B4") (pintype "bidirectional"))
    )
    (net (code "159") (name "TB2") (class "Default")
      (node (ref "D11") (pin "2") (pinfunction "CH2_2") (pintype "bidirectional"))
      (node (ref "D11") (pin "9") (pinfunction "N.C._3_9") (pintype "bidirectional"))
      (node (ref "R46") (pin "1") (pinfunction "1_1") (pintype "passive"))
      (node (ref "RN3") (pin "6") (pinfunction "2_6") (pintype "passive"))
      (node (ref "RN4") (pin "7") (pinfunction "2_7") (pintype "passive"))
      (node (ref "U$49") (pin "B5") (pinfunction "P$5_B5") (pintype "bidirectional"))
    )
    (net (code "160") (name "TB3") (class "Default")
      (node (ref "D11") (pin "4") (pinfunction "CH3_4") (pintype "bidirectional"))
      (node (ref "D11") (pin "7") (pinfunction "N.C._2_7") (pintype "bidirectional"))
      (node (ref "R45") (pin "1") (pinfunction "1_1") (pintype "passive"))
      (node (ref "RN3") (pin "7") (pinfunction "2_7") (pintype "passive"))
      (node (ref "RN4") (pin "6") (pinfunction "2_6") (pintype "passive"))
      (node (ref "U$49") (pin "B7") (pinfunction "P$7_B7") (pintype "bidirectional"))
    )
    (net (code "161") (name "TB4") (class "Default")
      (node (ref "D11") (pin "5") (pinfunction "CH4_5") (pintype "bidirectional"))
      (node (ref "D11") (pin "6") (pinfunction "N.C._1_6") (pintype "bidirectional"))
      (node (ref "R45") (pin "2") (pinfunction "2_2") (pintype "passive"))
      (node (ref "RN3") (pin "8") (pinfunction "2_8") (pintype "passive"))
      (node (ref "RN4") (pin "5") (pinfunction "2_5") (pintype "passive"))
      (node (ref "U$49") (pin "B8") (pinfunction "P$8_B8") (pintype "bidirectional"))
    )
    (net (code "162") (name "TC1") (class "Default")
      (node (ref "D12") (pin "1") (pinfunction "CH1_1") (pintype "bidirectional"))
      (node (ref "D12") (pin "10") (pinfunction "N.C._4_10") (pintype "bidirectional"))
      (node (ref "R44") (pin "2") (pinfunction "2_2") (pintype "passive"))
      (node (ref "RN5") (pin "5") (pinfunction "2_5") (pintype "passive"))
      (node (ref "RN6") (pin "8") (pinfunction "2_8") (pintype "passive"))
      (node (ref "U$49") (pin "C4") (pinfunction "P$4_C4") (pintype "bidirectional"))
    )
    (net (code "163") (name "TC2") (class "Default")
      (node (ref "D12") (pin "2") (pinfunction "CH2_2") (pintype "bidirectional"))
      (node (ref "D12") (pin "9") (pinfunction "N.C._3_9") (pintype "bidirectional"))
      (node (ref "R44") (pin "1") (pinfunction "1_1") (pintype "passive"))
      (node (ref "RN5") (pin "6") (pinfunction "2_6") (pintype "passive"))
      (node (ref "RN6") (pin "7") (pinfunction "2_7") (pintype "passive"))
      (node (ref "U$49") (pin "C5") (pinfunction "P$5_C5") (pintype "bidirectional"))
    )
    (net (code "164") (name "TC3") (class "Default")
      (node (ref "D12") (pin "4") (pinfunction "CH3_4") (pintype "bidirectional"))
      (node (ref "D12") (pin "7") (pinfunction "N.C._2_7") (pintype "bidirectional"))
      (node (ref "R43") (pin "1") (pinfunction "1_1") (pintype "passive"))
      (node (ref "RN5") (pin "7") (pinfunction "2_7") (pintype "passive"))
      (node (ref "RN6") (pin "6") (pinfunction "2_6") (pintype "passive"))
      (node (ref "U$49") (pin "C7") (pinfunction "P$7_C7") (pintype "bidirectional"))
    )
    (net (code "165") (name "TC4") (class "Default")
      (node (ref "D12") (pin "5") (pinfunction "CH4_5") (pintype "bidirectional"))
      (node (ref "D12") (pin "6") (pinfunction "N.C._1_6") (pintype "bidirectional"))
      (node (ref "R43") (pin "2") (pinfunction "2_2") (pintype "passive"))
      (node (ref "RN5") (pin "8") (pinfunction "2_8") (pintype "passive"))
      (node (ref "RN6") (pin "5") (pinfunction "2_5") (pintype "passive"))
      (node (ref "U$49") (pin "C8") (pinfunction "P$8_C8") (pintype "bidirectional"))
    )
    (net (code "166") (name "TD1") (class "Default")
      (node (ref "D13") (pin "1") (pinfunction "CH1_1") (pintype "bidirectional"))
      (node (ref "D13") (pin "10") (pinfunction "N.C._4_10") (pintype "bidirectional"))
      (node (ref "R41") (pin "2") (pinfunction "2_2") (pintype "passive"))
      (node (ref "RN7") (pin "5") (pinfunction "2_5") (pintype "passive"))
      (node (ref "RN9") (pin "8") (pinfunction "2_8") (pintype "passive"))
      (node (ref "U$49") (pin "D4") (pinfunction "P$4_D4") (pintype "bidirectional"))
    )
    (net (code "167") (name "TD2") (class "Default")
      (node (ref "D13") (pin "2") (pinfunction "CH2_2") (pintype "bidirectional"))
      (node (ref "D13") (pin "9") (pinfunction "N.C._3_9") (pintype "bidirectional"))
      (node (ref "R41") (pin "1") (pinfunction "1_1") (pintype "passive"))
      (node (ref "RN7") (pin "6") (pinfunction "2_6") (pintype "passive"))
      (node (ref "RN9") (pin "7") (pinfunction "2_7") (pintype "passive"))
      (node (ref "U$49") (pin "D5") (pinfunction "P$5_D5") (pintype "bidirectional"))
    )
    (net (code "168") (name "TD3") (class "Default")
      (node (ref "D13") (pin "4") (pinfunction "CH3_4") (pintype "bidirectional"))
      (node (ref "D13") (pin "7") (pinfunction "N.C._2_7") (pintype "bidirectional"))
      (node (ref "R42") (pin "1") (pinfunction "1_1") (pintype "passive"))
      (node (ref "RN7") (pin "7") (pinfunction "2_7") (pintype "passive"))
      (node (ref "RN9") (pin "6") (pinfunction "2_6") (pintype "passive"))
      (node (ref "U$49") (pin "D7") (pinfunction "P$7_D7") (pintype "bidirectional"))
    )
    (net (code "169") (name "TD4") (class "Default")
      (node (ref "D13") (pin "5") (pinfunction "CH4_5") (pintype "bidirectional"))
      (node (ref "D13") (pin "6") (pinfunction "N.C._1_6") (pintype "bidirectional"))
      (node (ref "R42") (pin "2") (pinfunction "2_2") (pintype "passive"))
      (node (ref "RN7") (pin "8") (pinfunction "2_8") (pintype "passive"))
      (node (ref "RN9") (pin "5") (pinfunction "2_5") (pintype "passive"))
      (node (ref "U$49") (pin "D8") (pinfunction "P$8_D8") (pintype "bidirectional"))
    )
    (net (code "170") (name "TE1") (class "Default")
      (node (ref "D14") (pin "1") (pinfunction "CH1_1") (pintype "bidirectional"))
      (node (ref "D14") (pin "10") (pinfunction "N.C._4_10") (pintype "bidirectional"))
      (node (ref "R55") (pin "1") (pinfunction "1_1") (pintype "passive"))
      (node (ref "RN10") (pin "5") (pinfunction "2_5") (pintype "passive"))
      (node (ref "RN15") (pin "8") (pinfunction "2_8") (pintype "passive"))
      (node (ref "U$50") (pin "A4") (pinfunction "P$4_A4") (pintype "bidirectional"))
    )
    (net (code "171") (name "TE2") (class "Default")
      (node (ref "D14") (pin "2") (pinfunction "CH2_2") (pintype "bidirectional"))
      (node (ref "D14") (pin "9") (pinfunction "N.C._3_9") (pintype "bidirectional"))
      (node (ref "R55") (pin "2") (pinfunction "2_2") (pintype "passive"))
      (node (ref "RN10") (pin "6") (pinfunction "2_6") (pintype "passive"))
      (node (ref "RN15") (pin "7") (pinfunction "2_7") (pintype "passive"))
      (node (ref "U$50") (pin "A5") (pinfunction "P$5_A5") (pintype "bidirectional"))
    )
    (net (code "172") (name "TE3") (class "Default")
      (node (ref "D14") (pin "4") (pinfunction "CH3_4") (pintype "bidirectional"))
      (node (ref "D14") (pin "7") (pinfunction "N.C._2_7") (pintype "bidirectional"))
      (node (ref "R56") (pin "2") (pinfunction "2_2") (pintype "passive"))
      (node (ref "RN10") (pin "7") (pinfunction "2_7") (pintype "passive"))
      (node (ref "RN15") (pin "6") (pinfunction "2_6") (pintype "passive"))
      (node (ref "U$50") (pin "A7") (pinfunction "P$7_A7") (pintype "bidirectional"))
    )
    (net (code "173") (name "TE4") (class "Default")
      (node (ref "D14") (pin "5") (pinfunction "CH4_5") (pintype "bidirectional"))
      (node (ref "D14") (pin "6") (pinfunction "N.C._1_6") (pintype "bidirectional"))
      (node (ref "R56") (pin "1") (pinfunction "1_1") (pintype "passive"))
      (node (ref "RN10") (pin "8") (pinfunction "2_8") (pintype "passive"))
      (node (ref "RN15") (pin "5") (pinfunction "2_5") (pintype "passive"))
      (node (ref "U$50") (pin "A8") (pinfunction "P$8_A8") (pintype "bidirectional"))
    )
    (net (code "174") (name "TF1") (class "Default")
      (node (ref "D15") (pin "1") (pinfunction "CH1_1") (pintype "bidirectional"))
      (node (ref "D15") (pin "10") (pinfunction "N.C._4_10") (pintype "bidirectional"))
      (node (ref "R51") (pin "1") (pinfunction "1_1") (pintype "passive"))
      (node (ref "RN11") (pin "5") (pinfunction "2_5") (pintype "passive"))
      (node (ref "RN17") (pin "8") (pinfunction "2_8") (pintype "passive"))
      (node (ref "U$50") (pin "B4") (pinfunction "P$4_B4") (pintype "bidirectional"))
    )
    (net (code "175") (name "TF2") (class "Default")
      (node (ref "D15") (pin "2") (pinfunction "CH2_2") (pintype "bidirectional"))
      (node (ref "D15") (pin "9") (pinfunction "N.C._3_9") (pintype "bidirectional"))
      (node (ref "R51") (pin "2") (pinfunction "2_2") (pintype "passive"))
      (node (ref "RN11") (pin "6") (pinfunction "2_6") (pintype "passive"))
      (node (ref "RN17") (pin "7") (pinfunction "2_7") (pintype "passive"))
      (node (ref "U$50") (pin "B5") (pinfunction "P$5_B5") (pintype "bidirectional"))
    )
    (net (code "176") (name "TF3") (class "Default")
      (node (ref "D15") (pin "4") (pinfunction "CH3_4") (pintype "bidirectional"))
      (node (ref "D15") (pin "7") (pinfunction "N.C._2_7") (pintype "bidirectional"))
      (node (ref "R52") (pin "2") (pinfunction "2_2") (pintype "passive"))
      (node (ref "RN11") (pin "7") (pinfunction "2_7") (pintype "passive"))
      (node (ref "RN17") (pin "6") (pinfunction "2_6") (pintype "passive"))
      (node (ref "U$50") (pin "B7") (pinfunction "P$7_B7") (pintype "bidirectional"))
    )
    (net (code "177") (name "TF4") (class "Default")
      (node (ref "D15") (pin "5") (pinfunction "CH4_5") (pintype "bidirectional"))
      (node (ref "D15") (pin "6") (pinfunction "N.C._1_6") (pintype "bidirectional"))
      (node (ref "R52") (pin "1") (pinfunction "1_1") (pintype "passive"))
      (node (ref "RN11") (pin "8") (pinfunction "2_8") (pintype "passive"))
      (node (ref "RN17") (pin "5") (pinfunction "2_5") (pintype "passive"))
      (node (ref "U$50") (pin "B8") (pinfunction "P$8_B8") (pintype "bidirectional"))
    )
    (net (code "178") (name "TG1") (class "Default")
      (node (ref "D16") (pin "1") (pinfunction "CH1_1") (pintype "bidirectional"))
      (node (ref "D16") (pin "10") (pinfunction "N.C._4_10") (pintype "bidirectional"))
      (node (ref "R53") (pin "1") (pinfunction "1_1") (pintype "passive"))
      (node (ref "RN12") (pin "5") (pinfunction "2_5") (pintype "passive"))
      (node (ref "RN19") (pin "8") (pinfunction "2_8") (pintype "passive"))
      (node (ref "U$50") (pin "C4") (pinfunction "P$4_C4") (pintype "bidirectional"))
    )
    (net (code "179") (name "TG2") (class "Default")
      (node (ref "D16") (pin "2") (pinfunction "CH2_2") (pintype "bidirectional"))
      (node (ref "D16") (pin "9") (pinfunction "N.C._3_9") (pintype "bidirectional"))
      (node (ref "R53") (pin "2") (pinfunction "2_2") (pintype "passive"))
      (node (ref "RN12") (pin "6") (pinfunction "2_6") (pintype "passive"))
      (node (ref "RN19") (pin "7") (pinfunction "2_7") (pintype "passive"))
      (node (ref "U$50") (pin "C5") (pinfunction "P$5_C5") (pintype "bidirectional"))
    )
    (net (code "180") (name "TG3") (class "Default")
      (node (ref "D16") (pin "4") (pinfunction "CH3_4") (pintype "bidirectional"))
      (node (ref "D16") (pin "7") (pinfunction "N.C._2_7") (pintype "bidirectional"))
      (node (ref "R54") (pin "2") (pinfunction "2_2") (pintype "passive"))
      (node (ref "RN12") (pin "7") (pinfunction "2_7") (pintype "passive"))
      (node (ref "RN19") (pin "6") (pinfunction "2_6") (pintype "passive"))
      (node (ref "U$50") (pin "C7") (pinfunction "P$7_C7") (pintype "bidirectional"))
    )
    (net (code "181") (name "TG4") (class "Default")
      (node (ref "D16") (pin "5") (pinfunction "CH4_5") (pintype "bidirectional"))
      (node (ref "D16") (pin "6") (pinfunction "N.C._1_6") (pintype "bidirectional"))
      (node (ref "R54") (pin "1") (pinfunction "1_1") (pintype "passive"))
      (node (ref "RN12") (pin "8") (pinfunction "2_8") (pintype "passive"))
      (node (ref "RN19") (pin "5") (pinfunction "2_5") (pintype "passive"))
      (node (ref "U$50") (pin "C8") (pinfunction "P$8_C8") (pintype "bidirectional"))
    )
    (net (code "182") (name "TH1") (class "Default")
      (node (ref "D17") (pin "1") (pinfunction "CH1_1") (pintype "bidirectional"))
      (node (ref "D17") (pin "10") (pinfunction "N.C._4_10") (pintype "bidirectional"))
      (node (ref "R49") (pin "1") (pinfunction "1_1") (pintype "passive"))
      (node (ref "RN13") (pin "5") (pinfunction "2_5") (pintype "passive"))
      (node (ref "RN21") (pin "8") (pinfunction "2_8") (pintype "passive"))
      (node (ref "U$50") (pin "D4") (pinfunction "P$4_D4") (pintype "bidirectional"))
    )
    (net (code "183") (name "TH2") (class "Default")
      (node (ref "D17") (pin "2") (pinfunction "CH2_2") (pintype "bidirectional"))
      (node (ref "D17") (pin "9") (pinfunction "N.C._3_9") (pintype "bidirectional"))
      (node (ref "R49") (pin "2") (pinfunction "2_2") (pintype "passive"))
      (node (ref "RN13") (pin "6") (pinfunction "2_6") (pintype "passive"))
      (node (ref "RN21") (pin "7") (pinfunction "2_7") (pintype "passive"))
      (node (ref "U$50") (pin "D5") (pinfunction "P$5_D5") (pintype "bidirectional"))
    )
    (net (code "184") (name "TH3") (class "Default")
      (node (ref "D17") (pin "4") (pinfunction "CH3_4") (pintype "bidirectional"))
      (node (ref "D17") (pin "7") (pinfunction "N.C._2_7") (pintype "bidirectional"))
      (node (ref "R50") (pin "2") (pinfunction "2_2") (pintype "passive"))
      (node (ref "RN13") (pin "7") (pinfunction "2_7") (pintype "passive"))
      (node (ref "RN21") (pin "6") (pinfunction "2_6") (pintype "passive"))
      (node (ref "U$50") (pin "D7") (pinfunction "P$7_D7") (pintype "bidirectional"))
    )
    (net (code "185") (name "TH4") (class "Default")
      (node (ref "D17") (pin "5") (pinfunction "CH4_5") (pintype "bidirectional"))
      (node (ref "D17") (pin "6") (pinfunction "N.C._1_6") (pintype "bidirectional"))
      (node (ref "R50") (pin "1") (pinfunction "1_1") (pintype "passive"))
      (node (ref "RN13") (pin "8") (pinfunction "2_8") (pintype "passive"))
      (node (ref "RN21") (pin "5") (pinfunction "2_5") (pintype "passive"))
      (node (ref "U$50") (pin "D8") (pinfunction "P$8_D8") (pintype "bidirectional"))
    )
    (net (code "186") (name "TXEN") (class "Default")
      (node (ref "IC1") (pin "F1") (pinfunction "PL14A_F1") (pintype "bidirectional"))
      (node (ref "U1") (pin "8") (pinfunction "TXE_N_8") (pintype "output"))
    )
    (net (code "187") (name "VCCAUX") (class "Default")
      (node (ref "C14") (pin "1") (pinfunction "1_1") (pintype "passive"))
      (node (ref "C16") (pin "1") (pinfunction "1_1") (pintype "passive"))
      (node (ref "IC1") (pin "G11") (pinfunction "VCCAUX_1_G11") (pintype "bidirectional"))
      (node (ref "IC1") (pin "L7") (pinfunction "VCCAUX_2_L7") (pintype "bidirectional"))
      (node (ref "U6") (pin "5") (pinfunction "VOUT_5") (pintype "output"))
    )
    (net (code "188") (name "VCCBOTTOM") (class "Default")
      (node (ref "C15") (pin "1") (pinfunction "1_1") (pintype "passive"))
      (node (ref "C17") (pin "1") (pinfunction "1_1") (pintype "passive"))
      (node (ref "C39") (pin "1") (pinfunction "1_1") (pintype "passive"))
      (node (ref "IC1") (pin "L6") (pinfunction "VCCIO8_L6") (pintype "bidirectional"))
      (node (ref "IC1") (pin "P10") (pinfunction "CFG_1_P10") (pintype "bidirectional"))
      (node (ref "R1") (pin "2") (pinfunction "2_2") (pintype "passive"))
      (node (ref "R10") (pin "1") (pinfunction "1_1") (pintype "passive"))
      (node (ref "R4") (pin "1") (pinfunction "1_1") (pintype "passive"))
      (node (ref "R7") (pin "1") (pinfunction "1_1") (pintype "passive"))
      (node (ref "U3") (pin "8") (pinfunction "VCC_8") (pintype "power_in"))
      (node (ref "U7") (pin "5") (pinfunction "VOUT_5") (pintype "output"))
    )
    (net (code "189") (name "VCCLR") (class "Default")
      (node (ref "C11") (pin "1") (pinfunction "1_1") (pintype "passive"))
      (node (ref "C32") (pin "1") (pinfunction "1_1") (pintype "passive"))
      (node (ref "C38") (pin "1") (pinfunction "1_1") (pintype "passive"))
      (node (ref "C5") (pin "1") (pinfunction "1_1") (pintype "passive"))
      (node (ref "IC1") (pin "H11") (pinfunction "VCCIO2_1_H11") (pintype "bidirectional"))
      (node (ref "IC1") (pin "J11") (pinfunction "VCCIO2_2_J11") (pintype "bidirectional"))
      (node (ref "IC1") (pin "J6") (pinfunction "VCCIO6_1_J6") (pintype "bidirectional"))
      (node (ref "IC1") (pin "J7") (pinfunction "VCCIO6_2_J7") (pintype "bidirectional"))
      (node (ref "IC1") (pin "K11") (pinfunction "VCCIO3_1_K11") (pintype "bidirectional"))
      (node (ref "IC1") (pin "L11") (pinfunction "VCCIO3_2_L11") (pintype "bidirectional"))
      (node (ref "J8") (pin "8") (pinfunction "8_8") (pintype "passive"))
      (node (ref "R25") (pin "2") (pinfunction "2_2") (pintype "passive"))
      (node (ref "RN1") (pin "2") (pinfunction "1_2") (pintype "passive"))
      (node (ref "RN1") (pin "4") (pinfunction "1_4") (pintype "passive"))
      (node (ref "RN10") (pin "2") (pinfunction "1_2") (pintype "passive"))
      (node (ref "RN10") (pin "4") (pinfunction "1_4") (pintype "passive"))
      (node (ref "RN11") (pin "2") (pinfunction "1_2") (pintype "passive"))
      (node (ref "RN11") (pin "4") (pinfunction "1_4") (pintype "passive"))
      (node (ref "RN12") (pin "2") (pinfunction "1_2") (pintype "passive"))
      (node (ref "RN12") (pin "4") (pinfunction "1_4") (pintype "passive"))
      (node (ref "RN13") (pin "2") (pinfunction "1_2") (pintype "passive"))
      (node (ref "RN13") (pin "4") (pinfunction "1_4") (pintype "passive"))
      (node (ref "RN3") (pin "2") (pinfunction "1_2") (pintype "passive"))
      (node (ref "RN3") (pin "4") (pinfunction "1_4") (pintype "passive"))
      (node (ref "RN5") (pin "2") (pinfunction "1_2") (pintype "passive"))
      (node (ref "RN5") (pin "4") (pinfunction "1_4") (pintype "passive"))
      (node (ref "RN7") (pin "2") (pinfunction "1_2") (pintype "passive"))
      (node (ref "RN7") (pin "4") (pinfunction "1_4") (pintype "passive"))
      (node (ref "U5") (pin "5") (pinfunction "VOUT_5") (pintype "output"))
    )
    (net (code "190") (name "VCCTOP") (class "Default")
      (node (ref "C1") (pin "1") (pinfunction "1_1") (pintype "passive"))
      (node (ref "C10") (pin "2") (pinfunction "2_2") (pintype "passive"))
      (node (ref "C19") (pin "2") (pinfunction "2_2") (pintype "passive"))
      (node (ref "C20") (pin "2") (pinfunction "2_2") (pintype "passive"))
      (node (ref "C24") (pin "2") (pinfunction "2_2") (pintype "passive"))
      (node (ref "C3") (pin "2") (pinfunction "2_2") (pintype "passive"))
      (node (ref "C30") (pin "2") (pinfunction "2_2") (pintype "passive"))
      (node (ref "C4") (pin "2") (pinfunction "2_2") (pintype "passive"))
      (node (ref "C6") (pin "2") (pinfunction "2_2") (pintype "passive"))
      (node (ref "C9") (pin "2") (pinfunction "2_2") (pintype "passive"))
      (node (ref "IC1") (pin "F10") (pinfunction "VCCIO1_1_F10") (pintype "bidirectional"))
      (node (ref "IC1") (pin "F11") (pinfunction "VCCIO1_2_F11") (pintype "bidirectional"))
      (node (ref "IC1") (pin "F6") (pinfunction "VCCIO0_1_F6") (pintype "bidirectional"))
      (node (ref "IC1") (pin "F7") (pinfunction "VCCIO0_2_F7") (pintype "bidirectional"))
      (node (ref "IC1") (pin "H6") (pinfunction "VCCIO7_1_H6") (pintype "bidirectional"))
      (node (ref "IC1") (pin "H7") (pinfunction "VCCIO7_2_H7") (pintype "bidirectional"))
      (node (ref "Q1") (pin "P$1") (pinfunction "OE_P$1") (pintype "input"))
      (node (ref "Q1") (pin "P$4") (pinfunction "VCC_P$4") (pintype "power_in"))
      (node (ref "R19") (pin "1") (pinfunction "1_1") (pintype "passive"))
      (node (ref "R26") (pin "2") (pinfunction "2_2") (pintype "passive"))
      (node (ref "R3") (pin "1") (pinfunction "1_1") (pintype "passive"))
      (node (ref "RN8") (pin "5") (pinfunction "2_5") (pintype "passive"))
      (node (ref "RN8") (pin "6") (pinfunction "2_6") (pintype "passive"))
      (node (ref "RN8") (pin "7") (pinfunction "2_7") (pintype "passive"))
      (node (ref "RN8") (pin "8") (pinfunction "2_8") (pintype "passive"))
      (node (ref "U1") (pin "14") (pinfunction "VCCIO_14") (pintype "power_in"))
      (node (ref "U1") (pin "20") (pinfunction "VCC33_20") (pintype "power_in"))
      (node (ref "U1") (pin "24") (pinfunction "VCC33_24") (pintype "power_in"))
      (node (ref "U1") (pin "28") (pinfunction "VDDA_28") (pintype "power_in"))
      (node (ref "U1") (pin "38") (pinfunction "VCC33_38") (pintype "power_in"))
      (node (ref "U1") (pin "49") (pinfunction "VCCIO_49") (pintype "power_in"))
      (node (ref "U1") (pin "59") (pinfunction "VCCIO_59") (pintype "power_in"))
      (node (ref "U1") (pin "68") (pinfunction "VCCIO_68") (pintype "power_in"))
      (node (ref "U4") (pin "5") (pinfunction "OUT_5") (pintype "output"))
    )
    (net (code "191") (name "VEXT") (class "Default")
      (node (ref "C21") (pin "1") (pinfunction "1_1") (pintype "passive"))
      (node (ref "C27") (pin "1") (pinfunction "1_1") (pintype "passive"))
      (node (ref "C28") (pin "1") (pinfunction "1_1") (pintype "passive"))
      (node (ref "C29") (pin "2") (pinfunction "2_2") (pintype "passive"))
      (node (ref "C31") (pin "1") (pinfunction "1_1") (pintype "passive"))
      (node (ref "C34") (pin "1") (pinfunction "1_1") (pintype "passive"))
      (node (ref "C37") (pin "1") (pinfunction "1_1") (pintype "passive"))
      (node (ref "C41") (pin "1") (pinfunction "1_1") (pintype "passive"))
      (node (ref "C42") (pin "1") (pinfunction "1_1") (pintype "passive"))
      (node (ref "C58") (pin "1") (pinfunction "1_1") (pintype "passive"))
      (node (ref "IC3") (pin "1") (pinfunction "VIN_1") (pintype "bidirectional"))
      (node (ref "IC3") (pin "3") (pinfunction "EN_3") (pintype "bidirectional"))
      (node (ref "J4") (pin "1") (pinfunction "1_1") (pintype "passive"))
      (node (ref "J4") (pin "2") (pinfunction "2_2") (pintype "passive"))
      (node (ref "JP3") (pin "2") (pinfunction "2_2") (pintype "passive"))
      (node (ref "LED1") (pin "3") (pinfunction "VDD_3") (pintype "bidirectional"))
      (node (ref "LED2") (pin "3") (pinfunction "VDD_3") (pintype "bidirectional"))
      (node (ref "LED3") (pin "3") (pinfunction "VDD_3") (pintype "bidirectional"))
      (node (ref "LED4") (pin "3") (pinfunction "VDD_3") (pintype "bidirectional"))
      (node (ref "LED5") (pin "3") (pinfunction "VDD_3") (pintype "bidirectional"))
      (node (ref "LED6") (pin "3") (pinfunction "VDD_3") (pintype "bidirectional"))
      (node (ref "LED7") (pin "3") (pinfunction "VDD_3") (pintype "bidirectional"))
      (node (ref "LED8") (pin "3") (pinfunction "VDD_3") (pintype "bidirectional"))
      (node (ref "LED9") (pin "3") (pinfunction "VDD_3") (pintype "bidirectional"))
      (node (ref "Q4") (pin "1") (pinfunction "S_1") (pintype "passive"))
      (node (ref "Q4") (pin "2") (pinfunction "S_2") (pintype "passive"))
      (node (ref "Q4") (pin "3") (pinfunction "S_3") (pintype "passive"))
      (node (ref "R6") (pin "1") (pinfunction "1_1") (pintype "passive"))
      (node (ref "R8") (pin "2") (pinfunction "2_2") (pintype "passive"))
      (node (ref "U1") (pin "37") (pinfunction "VBUS_37") (pintype "input"))
      (node (ref "U4") (pin "1") (pinfunction "IN_1") (pintype "input"))
      (node (ref "U4") (pin "3") (pinfunction "EN_3") (pintype "input"))
      (node (ref "U5") (pin "1") (pinfunction "VIN_1") (pintype "input"))
      (node (ref "U5") (pin "3") (pinfunction "ON/OFF_3") (pintype "input"))
      (node (ref "U6") (pin "1") (pinfunction "VIN_1") (pintype "input"))
      (node (ref "U6") (pin "3") (pinfunction "ON/OFF_3") (pintype "input"))
      (node (ref "U7") (pin "1") (pinfunction "VIN_1") (pintype "input"))
      (node (ref "U7") (pin "3") (pinfunction "ON/OFF_3") (pintype "input"))
      (node (ref "U8") (pin "2") (pinfunction "VDD_2") (pintype "power_in"))
    )
    (net (code "192") (name "VOUT") (class "Default")
      (node (ref "C50") (pin "1") (pinfunction "1_1") (pintype "passive"))
      (node (ref "D2") (pin "A") (pinfunction "A_A") (pintype "passive"))
      (node (ref "D3") (pin "A") (pinfunction "A_A") (pintype "passive"))
      (node (ref "D4") (pin "A") (pinfunction "A_A") (pintype "passive"))
      (node (ref "D5") (pin "A") (pinfunction "A_A") (pintype "passive"))
      (node (ref "D6") (pin "A") (pinfunction "A_A") (pintype "passive"))
      (node (ref "D7") (pin "A") (pinfunction "A_A") (pintype "passive"))
      (node (ref "D8") (pin "A") (pinfunction "A_A") (pintype "passive"))
      (node (ref "D9") (pin "A") (pinfunction "A_A") (pintype "passive"))
      (node (ref "R22") (pin "1") (pinfunction "1_1") (pintype "passive"))
      (node (ref "R24") (pin "2") (pinfunction "2_2") (pintype "passive"))
    )
    (net (code "193") (name "WAKEUP_N") (class "Default")
      (node (ref "J4") (pin "7") (pinfunction "7_7") (pintype "passive"))
      (node (ref "R3") (pin "2") (pinfunction "2_2") (pintype "passive"))
      (node (ref "U1") (pin "16") (pinfunction "WAKEUP_N_16") (pintype "bidirectional"))
    )
    (net (code "194") (name "WRN") (class "Default")
      (node (ref "IC1") (pin "G1") (pinfunction "PL20A_G1") (pintype "bidirectional"))
      (node (ref "RN8") (pin "3") (pinfunction "1_3") (pintype "passive"))
      (node (ref "U1") (pin "11") (pinfunction "WR_N_11") (pintype "input"))
    )
    (net (code "195") (name "XI") (class "Default")
      (node (ref "C36") (pin "2") (pinfunction "2_2") (pintype "passive"))
      (node (ref "Q3") (pin "1") (pinfunction "1_1") (pintype "passive"))
      (node (ref "U1") (pin "21") (pinfunction "XI_21") (pintype "input"))
    )
    (net (code "196") (name "XO") (class "Default")
      (node (ref "C35") (pin "2") (pinfunction "2_2") (pintype "passive"))
      (node (ref "Q3") (pin "3") (pinfunction "3_3") (pintype "passive"))
      (node (ref "U1") (pin "22") (pinfunction "XO_22") (pintype "output"))
    )
    (net (code "197") (name "unconnected-(IC1-PB6A-PadR7)") (class "Default")
      (node (ref "IC1") (pin "R7") (pinfunction "PB6A_R7") (pintype "bidirectional"))
    )
    (net (code "198") (name "unconnected-(IC1-PB6B-PadP7)") (class "Default")
      (node (ref "IC1") (pin "P7") (pinfunction "PB6B_P7") (pintype "bidirectional"))
    )
    (net (code "199") (name "unconnected-(IC1-PB9A-PadN7)") (class "Default")
      (node (ref "IC1") (pin "N7") (pinfunction "PB9A_N7") (pintype "bidirectional"))
    )
    (net (code "200") (name "unconnected-(IC1-PB9B-PadM7)") (class "Default")
      (node (ref "IC1") (pin "M7") (pinfunction "PB9B_M7") (pintype "bidirectional"))
    )
    (net (code "201") (name "unconnected-(IC1-PB13A-PadR8)") (class "Default")
      (node (ref "IC1") (pin "R8") (pinfunction "PB13A_R8") (pintype "bidirectional"))
    )
    (net (code "202") (name "unconnected-(IC1-PB13B-PadP8)") (class "Default")
      (node (ref "IC1") (pin "P8") (pinfunction "PB13B_P8") (pintype "bidirectional"))
    )
    (net (code "203") (name "unconnected-(IC1-PB15B-PadM8)") (class "Default")
      (node (ref "IC1") (pin "M8") (pinfunction "PB15B_M8") (pintype "bidirectional"))
    )
    (net (code "204") (name "unconnected-(IC1-PB18A-PadM9)") (class "Default")
      (node (ref "IC1") (pin "M9") (pinfunction "PB18A_M9") (pintype "bidirectional"))
    )
    (net (code "205") (name "unconnected-(IC1-PL2C-PadC3)") (class "Default")
      (node (ref "IC1") (pin "C3") (pinfunction "PL2C_C3") (pintype "bidirectional"))
    )
    (net (code "206") (name "unconnected-(IC1-PL2D-PadD3)") (class "Default")
      (node (ref "IC1") (pin "D3") (pinfunction "PL2D_D3") (pintype "bidirectional"))
    )
    (net (code "207") (name "unconnected-(IC1-PL5B-PadC2)") (class "Default")
      (node (ref "IC1") (pin "C2") (pinfunction "PL5B_C2") (pintype "bidirectional"))
    )
    (net (code "208") (name "unconnected-(IC1-PL5C-PadE3)") (class "Default")
      (node (ref "IC1") (pin "E3") (pinfunction "PL5C_E3") (pintype "bidirectional"))
    )
    (net (code "209") (name "unconnected-(IC1-PL5D-PadF3)") (class "Default")
      (node (ref "IC1") (pin "F3") (pinfunction "PL5D_F3") (pintype "bidirectional"))
    )
    (net (code "210") (name "unconnected-(IC1-PL8B-PadE2)") (class "Default")
      (node (ref "IC1") (pin "E2") (pinfunction "PL8B_E2") (pintype "bidirectional"))
    )
    (net (code "211") (name "unconnected-(IC1-PL8C-PadF4)") (class "Default")
      (node (ref "IC1") (pin "F4") (pinfunction "PL8C_F4") (pintype "bidirectional"))
    )
    (net (code "212") (name "unconnected-(IC1-PL8D-PadF5)") (class "Default")
      (node (ref "IC1") (pin "F5") (pinfunction "PL8D_F5") (pintype "bidirectional"))
    )
    (net (code "213") (name "unconnected-(IC1-PL11A-PadG5)") (class "Default")
      (node (ref "IC1") (pin "G5") (pinfunction "PL11A_G5") (pintype "bidirectional"))
    )
    (net (code "214") (name "unconnected-(IC1-PL11B-PadG4)") (class "Default")
      (node (ref "IC1") (pin "G4") (pinfunction "PL11B_G4") (pintype "bidirectional"))
    )
    (net (code "215") (name "unconnected-(IC1-PL11C-PadF2)") (class "Default")
      (node (ref "IC1") (pin "F2") (pinfunction "PL11C_F2") (pintype "bidirectional"))
    )
    (net (code "216") (name "unconnected-(IC1-PL14C-PadG3)") (class "Default")
      (node (ref "IC1") (pin "G3") (pinfunction "PL14C_G3") (pintype "bidirectional"))
    )
    (net (code "217") (name "unconnected-(IC1-PL14D-PadH3)") (class "Default")
      (node (ref "IC1") (pin "H3") (pinfunction "PL14D_H3") (pintype "bidirectional"))
    )
    (net (code "218") (name "unconnected-(IC1-PL17A-PadH5)") (class "Default")
      (node (ref "IC1") (pin "H5") (pinfunction "PL17A_H5") (pintype "bidirectional"))
    )
    (net (code "219") (name "unconnected-(IC1-PL17B-PadH4)") (class "Default")
      (node (ref "IC1") (pin "H4") (pinfunction "PL17B_H4") (pintype "bidirectional"))
    )
    (net (code "220") (name "unconnected-(IC1-PL17C-PadJ4)") (class "Default")
      (node (ref "IC1") (pin "J4") (pinfunction "PL17C_J4") (pintype "bidirectional"))
    )
    (net (code "221") (name "unconnected-(IC1-PL17D-PadJ5)") (class "Default")
      (node (ref "IC1") (pin "J5") (pinfunction "PL17D_J5") (pintype "bidirectional"))
    )
    (net (code "222") (name "unconnected-(IC1-PL20B-PadH2)") (class "Default")
      (node (ref "IC1") (pin "H2") (pinfunction "PL20B_H2") (pintype "bidirectional"))
    )
    (net (code "223") (name "unconnected-(IC1-PL20C-PadJ3)") (class "Default")
      (node (ref "IC1") (pin "J3") (pinfunction "PL20C_J3") (pintype "bidirectional"))
    )
    (net (code "224") (name "unconnected-(IC1-PL20D-PadK3)") (class "Default")
      (node (ref "IC1") (pin "K3") (pinfunction "PL20D_K3") (pintype "bidirectional"))
    )
    (net (code "225") (name "unconnected-(IC1-PL23B-PadJ2)") (class "Default")
      (node (ref "IC1") (pin "J2") (pinfunction "PL23B_J2") (pintype "bidirectional"))
    )
    (net (code "226") (name "unconnected-(IC1-PL29A-PadK4)") (class "Default")
      (node (ref "IC1") (pin "K4") (pinfunction "PL29A_K4") (pintype "bidirectional"))
    )
    (net (code "227") (name "unconnected-(IC1-PL29B-PadK5)") (class "Default")
      (node (ref "IC1") (pin "K5") (pinfunction "PL29B_K5") (pintype "bidirectional"))
    )
    (net (code "228") (name "unconnected-(IC1-PL29C-PadL4)") (class "Default")
      (node (ref "IC1") (pin "L4") (pinfunction "PL29C_L4") (pintype "bidirectional"))
    )
    (net (code "229") (name "unconnected-(IC1-PL29D-PadL5)") (class "Default")
      (node (ref "IC1") (pin "L5") (pinfunction "PL29D_L5") (pintype "bidirectional"))
    )
    (net (code "230") (name "unconnected-(IC1-PL32D-PadM3)") (class "Default")
      (node (ref "IC1") (pin "M3") (pinfunction "PL32D_M3") (pintype "bidirectional"))
    )
    (net (code "231") (name "unconnected-(IC1-PL35C-PadM4)") (class "Default")
      (node (ref "IC1") (pin "M4") (pinfunction "PL35C_M4") (pintype "bidirectional"))
    )
    (net (code "232") (name "unconnected-(IC1-PL35D-PadN3)") (class "Default")
      (node (ref "IC1") (pin "N3") (pinfunction "PL35D_N3") (pintype "bidirectional"))
    )
    (net (code "233") (name "unconnected-(IC1-PL44C-PadM5)") (class "Default")
      (node (ref "IC1") (pin "M5") (pinfunction "PL44C_M5") (pintype "bidirectional"))
    )
    (net (code "234") (name "unconnected-(IC1-PL44D-PadN5)") (class "Default")
      (node (ref "IC1") (pin "N5") (pinfunction "PL44D_N5") (pintype "bidirectional"))
    )
    (net (code "235") (name "unconnected-(IC1-PL47A-PadM6)") (class "Default")
      (node (ref "IC1") (pin "M6") (pinfunction "PL47A_M6") (pintype "bidirectional"))
    )
    (net (code "236") (name "unconnected-(IC1-PL47B-PadN6)") (class "Default")
      (node (ref "IC1") (pin "N6") (pinfunction "PL47B_N6") (pintype "bidirectional"))
    )
    (net (code "237") (name "unconnected-(IC1-PL47C-PadP6)") (class "Default")
      (node (ref "IC1") (pin "P6") (pinfunction "PL47C_P6") (pintype "bidirectional"))
    )
    (net (code "238") (name "unconnected-(IC1-PL47D-PadP5)") (class "Default")
      (node (ref "IC1") (pin "P5") (pinfunction "PL47D_P5") (pintype "bidirectional"))
    )
    (net (code "239") (name "unconnected-(IC1-PR2C-PadC14)") (class "Default")
      (node (ref "IC1") (pin "C14") (pinfunction "PR2C_C14") (pintype "bidirectional"))
    )
    (net (code "240") (name "unconnected-(IC1-PR2D-PadD14)") (class "Default")
      (node (ref "IC1") (pin "D14") (pinfunction "PR2D_D14") (pintype "bidirectional"))
    )
    (net (code "241") (name "unconnected-(IC1-PR5B-PadC15)") (class "Default")
      (node (ref "IC1") (pin "C15") (pinfunction "PR5B_C15") (pintype "bidirectional"))
    )
    (net (code "242") (name "unconnected-(IC1-PR5C-PadE14)") (class "Default")
      (node (ref "IC1") (pin "E14") (pinfunction "PR5C_E14") (pintype "bidirectional"))
    )
    (net (code "243") (name "unconnected-(IC1-PR5D-PadF14)") (class "Default")
      (node (ref "IC1") (pin "F14") (pinfunction "PR5D_F14") (pintype "bidirectional"))
    )
    (net (code "244") (name "unconnected-(IC1-PR8B-PadE15)") (class "Default")
      (node (ref "IC1") (pin "E15") (pinfunction "PR8B_E15") (pintype "bidirectional"))
    )
    (net (code "245") (name "unconnected-(IC1-PR8C-PadF13)") (class "Default")
      (node (ref "IC1") (pin "F13") (pinfunction "PR8C_F13") (pintype "bidirectional"))
    )
    (net (code "246") (name "unconnected-(IC1-PR8D-PadF12)") (class "Default")
      (node (ref "IC1") (pin "F12") (pinfunction "PR8D_F12") (pintype "bidirectional"))
    )
    (net (code "247") (name "unconnected-(IC1-PR11A-PadG12)") (class "Default")
      (node (ref "IC1") (pin "G12") (pinfunction "PR11A_G12") (pintype "bidirectional"))
    )
    (net (code "248") (name "unconnected-(IC1-PR11B-PadG13)") (class "Default")
      (node (ref "IC1") (pin "G13") (pinfunction "PR11B_G13") (pintype "bidirectional"))
    )
    (net (code "249") (name "unconnected-(IC1-PR11C-PadF15)") (class "Default")
      (node (ref "IC1") (pin "F15") (pinfunction "PR11C_F15") (pintype "bidirectional"))
    )
    (net (code "250") (name "unconnected-(IC1-PR14B-PadG15)") (class "Default")
      (node (ref "IC1") (pin "G15") (pinfunction "PR14B_G15") (pintype "bidirectional"))
    )
    (net (code "251") (name "unconnected-(IC1-PR14C-PadG14)") (class "Default")
      (node (ref "IC1") (pin "G14") (pinfunction "PR14C_G14") (pintype "bidirectional"))
    )
    (net (code "252") (name "unconnected-(IC1-PR14D-PadH14)") (class "Default")
      (node (ref "IC1") (pin "H14") (pinfunction "PR14D_H14") (pintype "bidirectional"))
    )
    (net (code "253") (name "unconnected-(IC1-PR17A-PadH12)") (class "Default")
      (node (ref "IC1") (pin "H12") (pinfunction "PR17A_H12") (pintype "bidirectional"))
    )
    (net (code "254") (name "unconnected-(IC1-PR17B-PadH13)") (class "Default")
      (node (ref "IC1") (pin "H13") (pinfunction "PR17B_H13") (pintype "bidirectional"))
    )
    (net (code "255") (name "unconnected-(IC1-PR17C-PadJ13)") (class "Default")
      (node (ref "IC1") (pin "J13") (pinfunction "PR17C_J13") (pintype "bidirectional"))
    )
    (net (code "256") (name "unconnected-(IC1-PR17D-PadJ12)") (class "Default")
      (node (ref "IC1") (pin "J12") (pinfunction "PR17D_J12") (pintype "bidirectional"))
    )
    (net (code "257") (name "unconnected-(IC1-PR20C-PadJ14)") (class "Default")
      (node (ref "IC1") (pin "J14") (pinfunction "PR20C_J14") (pintype "bidirectional"))
    )
    (net (code "258") (name "unconnected-(IC1-PR20D-PadK14)") (class "Default")
      (node (ref "IC1") (pin "K14") (pinfunction "PR20D_K14") (pintype "bidirectional"))
    )
    (net (code "259") (name "unconnected-(IC1-PR23D-PadK15)") (class "Default")
      (node (ref "IC1") (pin "K15") (pinfunction "PR23D_K15") (pintype "bidirectional"))
    )
    (net (code "260") (name "unconnected-(IC1-PR26D-PadM15)") (class "Default")
      (node (ref "IC1") (pin "M15") (pinfunction "PR26D_M15") (pintype "bidirectional"))
    )
    (net (code "261") (name "unconnected-(IC1-PR29A-PadK13)") (class "Default")
      (node (ref "IC1") (pin "K13") (pinfunction "PR29A_K13") (pintype "bidirectional"))
    )
    (net (code "262") (name "unconnected-(IC1-PR29B-PadK12)") (class "Default")
      (node (ref "IC1") (pin "K12") (pinfunction "PR29B_K12") (pintype "bidirectional"))
    )
    (net (code "263") (name "unconnected-(IC1-PR29C-PadL13)") (class "Default")
      (node (ref "IC1") (pin "L13") (pinfunction "PR29C_L13") (pintype "bidirectional"))
    )
    (net (code "264") (name "unconnected-(IC1-PR29D-PadL12)") (class "Default")
      (node (ref "IC1") (pin "L12") (pinfunction "PR29D_L12") (pintype "bidirectional"))
    )
    (net (code "265") (name "unconnected-(IC1-PR32C-PadL14)") (class "Default")
      (node (ref "IC1") (pin "L14") (pinfunction "PR32C_L14") (pintype "bidirectional"))
    )
    (net (code "266") (name "unconnected-(IC1-PR32D-PadM14)") (class "Default")
      (node (ref "IC1") (pin "M14") (pinfunction "PR32D_M14") (pintype "bidirectional"))
    )
    (net (code "267") (name "unconnected-(IC1-PR35C-PadM13)") (class "Default")
      (node (ref "IC1") (pin "M13") (pinfunction "PR35C_M13") (pintype "bidirectional"))
    )
    (net (code "268") (name "unconnected-(IC1-PR35D-PadN14)") (class "Default")
      (node (ref "IC1") (pin "N14") (pinfunction "PR35D_N14") (pintype "bidirectional"))
    )
    (net (code "269") (name "unconnected-(IC1-PR38A-PadN13)") (class "Default")
      (node (ref "IC1") (pin "N13") (pinfunction "PR38A_N13") (pintype "bidirectional"))
    )
    (net (code "270") (name "unconnected-(IC1-PR38B-PadP14)") (class "Default")
      (node (ref "IC1") (pin "P14") (pinfunction "PR38B_P14") (pintype "bidirectional"))
    )
    (net (code "271") (name "unconnected-(IC1-PR41A-PadP13)") (class "Default")
      (node (ref "IC1") (pin "P13") (pinfunction "PR41A_P13") (pintype "bidirectional"))
    )
    (net (code "272") (name "unconnected-(IC1-PR41B-PadR14)") (class "Default")
      (node (ref "IC1") (pin "R14") (pinfunction "PR41B_R14") (pintype "bidirectional"))
    )
    (net (code "273") (name "unconnected-(IC1-PR44C-PadM12)") (class "Default")
      (node (ref "IC1") (pin "M12") (pinfunction "PR44C_M12") (pintype "bidirectional"))
    )
    (net (code "274") (name "unconnected-(IC1-PR44D-PadN12)") (class "Default")
      (node (ref "IC1") (pin "N12") (pinfunction "PR44D_N12") (pintype "bidirectional"))
    )
    (net (code "275") (name "unconnected-(IC1-PR47A-PadM11)") (class "Default")
      (node (ref "IC1") (pin "M11") (pinfunction "PR47A_M11") (pintype "bidirectional"))
    )
    (net (code "276") (name "unconnected-(IC1-PR47B-PadN11)") (class "Default")
      (node (ref "IC1") (pin "N11") (pinfunction "PR47B_N11") (pintype "bidirectional"))
    )
    (net (code "277") (name "unconnected-(IC1-PR47C-PadP11)") (class "Default")
      (node (ref "IC1") (pin "P11") (pinfunction "PR47C_P11") (pintype "bidirectional"))
    )
    (net (code "278") (name "unconnected-(IC1-PR47D-PadP12)") (class "Default")
      (node (ref "IC1") (pin "P12") (pinfunction "PR47D_P12") (pintype "bidirectional"))
    )
    (net (code "279") (name "unconnected-(IC1-PT11A-PadC4)") (class "Default")
      (node (ref "IC1") (pin "C4") (pinfunction "PT11A_C4") (pintype "bidirectional"))
    )
    (net (code "280") (name "unconnected-(IC1-PT13A-PadE5)") (class "Default")
      (node (ref "IC1") (pin "E5") (pinfunction "PT13A_E5") (pintype "bidirectional"))
    )
    (net (code "281") (name "unconnected-(IC1-PT13B-PadD5)") (class "Default")
      (node (ref "IC1") (pin "D5") (pinfunction "PT13B_D5") (pintype "bidirectional"))
    )
    (net (code "282") (name "unconnected-(IC1-PT20A-PadE6)") (class "Default")
      (node (ref "IC1") (pin "E6") (pinfunction "PT20A_E6") (pintype "bidirectional"))
    )
    (net (code "283") (name "unconnected-(IC1-PT20B-PadD6)") (class "Default")
      (node (ref "IC1") (pin "D6") (pinfunction "PT20B_D6") (pintype "bidirectional"))
    )
    (net (code "284") (name "unconnected-(IC1-PT22A-PadC6)") (class "Default")
      (node (ref "IC1") (pin "C6") (pinfunction "PT22A_C6") (pintype "bidirectional"))
    )
    (net (code "285") (name "unconnected-(IC1-PT24A-PadE7)") (class "Default")
      (node (ref "IC1") (pin "E7") (pinfunction "PT24A_E7") (pintype "bidirectional"))
    )
    (net (code "286") (name "unconnected-(IC1-PT24B-PadD7)") (class "Default")
      (node (ref "IC1") (pin "D7") (pinfunction "PT24B_D7") (pintype "bidirectional"))
    )
    (net (code "287") (name "unconnected-(IC1-PT27A-PadC7)") (class "Default")
      (node (ref "IC1") (pin "C7") (pinfunction "PT27A_C7") (pintype "bidirectional"))
    )
    (net (code "288") (name "unconnected-(IC1-PT33A-PadE8)") (class "Default")
      (node (ref "IC1") (pin "E8") (pinfunction "PT33A_E8") (pintype "bidirectional"))
    )
    (net (code "289") (name "unconnected-(IC1-PT35A-PadC8)") (class "Default")
      (node (ref "IC1") (pin "C8") (pinfunction "PT35A_C8") (pintype "bidirectional"))
    )
    (net (code "290") (name "unconnected-(IC1-PT38B-PadC9)") (class "Default")
      (node (ref "IC1") (pin "C9") (pinfunction "PT38B_C9") (pintype "bidirectional"))
    )
    (net (code "291") (name "unconnected-(IC1-PT40A-PadD9)") (class "Default")
      (node (ref "IC1") (pin "D9") (pinfunction "PT40A_D9") (pintype "bidirectional"))
    )
    (net (code "292") (name "unconnected-(IC1-PT40B-PadE9)") (class "Default")
      (node (ref "IC1") (pin "E9") (pinfunction "PT40B_E9") (pintype "bidirectional"))
    )
    (net (code "293") (name "unconnected-(IC1-PT44B-PadC10)") (class "Default")
      (node (ref "IC1") (pin "C10") (pinfunction "PT44B_C10") (pintype "bidirectional"))
    )
    (net (code "294") (name "unconnected-(IC1-PT47A-PadD10)") (class "Default")
      (node (ref "IC1") (pin "D10") (pinfunction "PT47A_D10") (pintype "bidirectional"))
    )
    (net (code "295") (name "unconnected-(IC1-PT47B-PadE10)") (class "Default")
      (node (ref "IC1") (pin "E10") (pinfunction "PT47B_E10") (pintype "bidirectional"))
    )
    (net (code "296") (name "unconnected-(IC1-PT49B-PadC11)") (class "Default")
      (node (ref "IC1") (pin "C11") (pinfunction "PT49B_C11") (pintype "bidirectional"))
    )
    (net (code "297") (name "unconnected-(IC1-PT51A-PadD11)") (class "Default")
      (node (ref "IC1") (pin "D11") (pinfunction "PT51A_D11") (pintype "bidirectional"))
    )
    (net (code "298") (name "unconnected-(IC1-PT51B-PadE11)") (class "Default")
      (node (ref "IC1") (pin "E11") (pinfunction "PT51B_E11") (pintype "bidirectional"))
    )
    (net (code "299") (name "unconnected-(IC1-PT56B-PadC12)") (class "Default")
      (node (ref "IC1") (pin "C12") (pinfunction "PT56B_C12") (pintype "bidirectional"))
    )
    (net (code "300") (name "unconnected-(IC1-PT58A-PadD12)") (class "Default")
      (node (ref "IC1") (pin "D12") (pinfunction "PT58A_D12") (pintype "bidirectional"))
    )
    (net (code "301") (name "unconnected-(IC1-PT58B-PadE12)") (class "Default")
      (node (ref "IC1") (pin "E12") (pinfunction "PT58B_E12") (pintype "bidirectional"))
    )
    (net (code "302") (name "unconnected-(LED6-DOUT-Pad1)") (class "Default")
      (node (ref "LED6") (pin "1") (pinfunction "DOUT_1") (pintype "bidirectional"))
    )
    (net (code "303") (name "unconnected-(U3-HOLD-Pad7)") (class "Default")
      (node (ref "U3") (pin "7") (pinfunction "HOLD_7") (pintype "bidirectional"))
    )
    (net (code "304") (name "unconnected-(U3-WP-Pad3)") (class "Default")
      (node (ref "U3") (pin "3") (pinfunction "WP_3") (pintype "bidirectional"))
    )
    (net (code "305") (name "unconnected-(U4-NC-Pad4)") (class "Default")
      (node (ref "U4") (pin "4") (pinfunction "NC_4") (pintype "no_connect"))
    )
    (net (code "306") (name "unconnected-(U5-BYPASS-Pad4)") (class "Default")
      (node (ref "U5") (pin "4") (pinfunction "BYPASS_4") (pintype "bidirectional"))
    )
    (net (code "307") (name "unconnected-(U6-BYPASS-Pad4)") (class "Default")
      (node (ref "U6") (pin "4") (pinfunction "BYPASS_4") (pintype "bidirectional"))
    )
    (net (code "308") (name "unconnected-(U7-BYPASS-Pad4)") (class "Default")
      (node (ref "U7") (pin "4") (pinfunction "BYPASS_4") (pintype "bidirectional"))
    )
    (net (code "309") (name "unconnected-(U8-NC-Pad1)") (class "Default")
      (node (ref "U8") (pin "1") (pinfunction "NC_1") (pintype "bidirectional"))
    )
  )
)
